# collpitss.net
KiCad netlist of a schematic drawn in EAGLE
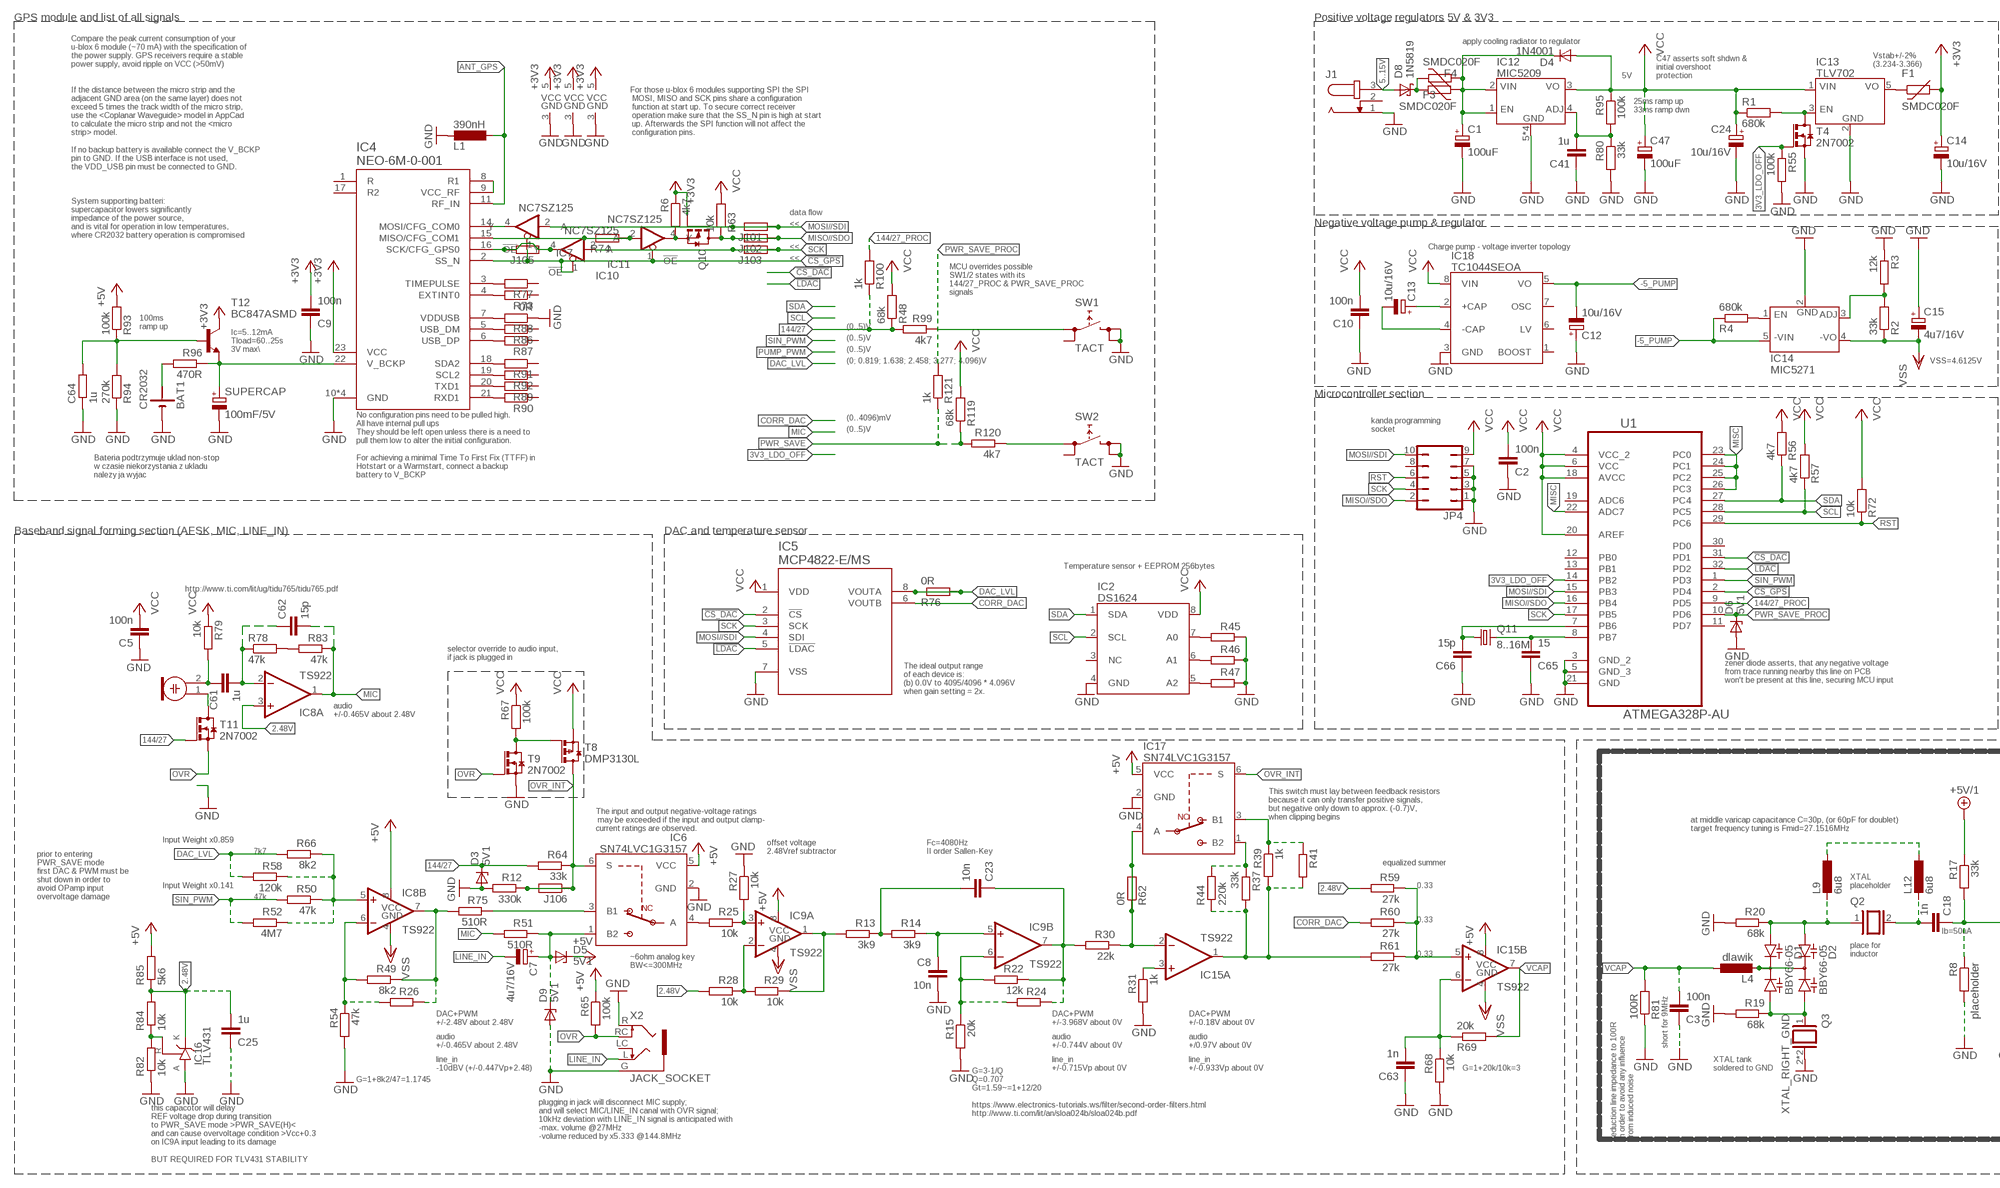
[diagram p0: schematic, sheet 1, part 1 of 2]
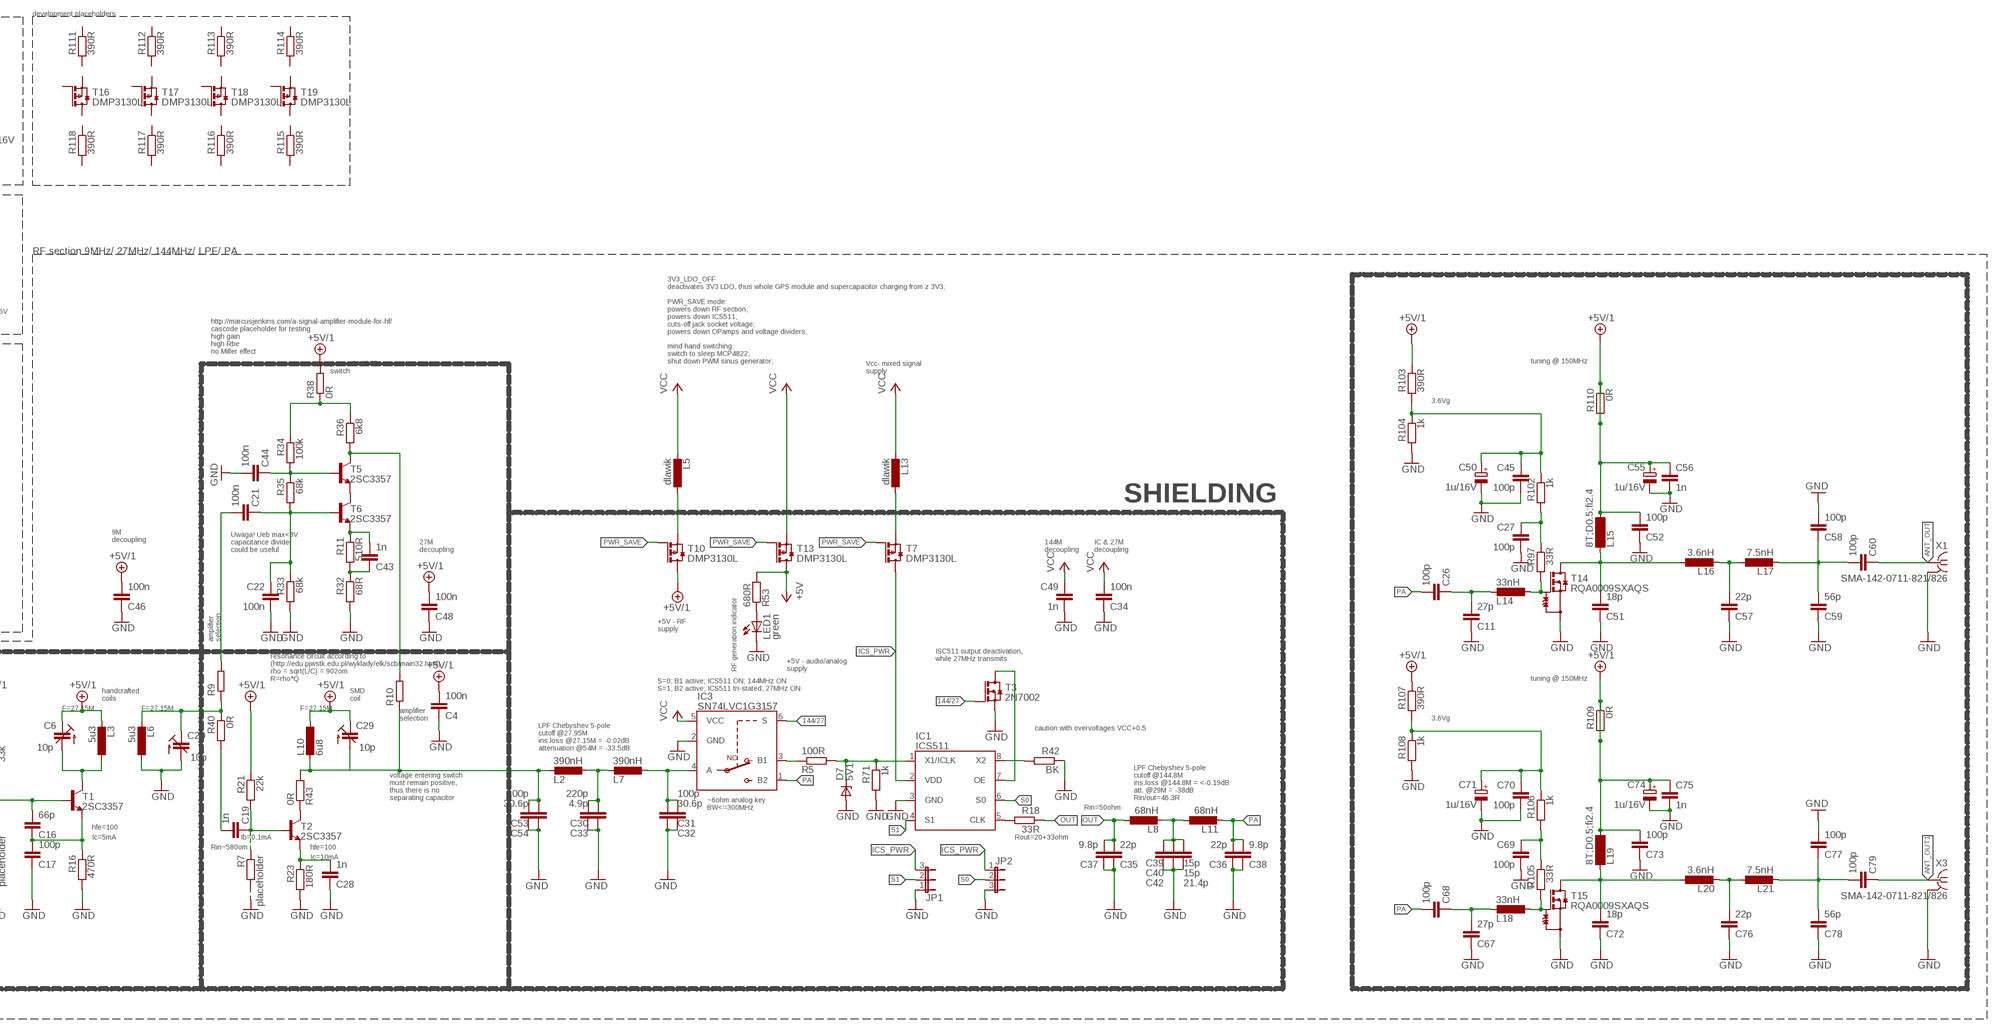
[diagram p1: schematic, sheet 1, part 2 of 2]

(export (version "E")
  (design (tool "Eeschema 10.0.6"))
  (components
    (comp (ref "BAT1")
      (value "CR2032")
      (footprint "eagle-import:CR2032_HOLDER")
      (libsource (lib "eagle-import") (part "CR2032"))
    )
    (comp (ref "C1")
      (value "100uF")
      (footprint "eagle-import:153CLV-0605")
      (libsource (lib "eagle-import") (part "CPOL-EU153CLV-0605"))
    )
    (comp (ref "C2")
      (value "100n")
      (footprint "eagle-import:C0805")
      (libsource (lib "eagle-import") (part "C-EUC0805"))
    )
    (comp (ref "C3")
      (value "100n")
      (footprint "eagle-import:C0805")
      (libsource (lib "eagle-import") (part "C-EUC0805"))
    )
    (comp (ref "C4")
      (value "100n")
      (footprint "eagle-import:C0805")
      (libsource (lib "eagle-import") (part "C-EUC0805"))
    )
    (comp (ref "C5")
      (value "100n")
      (footprint "eagle-import:C0805")
      (libsource (lib "eagle-import") (part "C-EUC0805"))
    )
    (comp (ref "C6")
      (value "10p")
      (footprint "eagle-import:TZC3_SERIES")
      (libsource (lib "eagle-import") (part "C_TRIMM"))
    )
    (comp (ref "C7")
      (value "4u7/16V")
      (footprint "eagle-import:TANTAL_3216_")
      (libsource (lib "eagle-import") (part "TANTAL_POLY{dblquote}3218{dblquote}"))
    )
    (comp (ref "C8")
      (value "10n")
      (footprint "eagle-import:C0805")
      (libsource (lib "eagle-import") (part "C-EUC0805"))
    )
    (comp (ref "C9")
      (value "100n")
      (footprint "eagle-import:C0805")
      (libsource (lib "eagle-import") (part "C-EUC0805"))
    )
    (comp (ref "C10")
      (value "100n")
      (footprint "eagle-import:C0805")
      (libsource (lib "eagle-import") (part "C-EUC0805"))
    )
    (comp (ref "C11")
      (value "27p")
      (footprint "eagle-import:C0805")
      (libsource (lib "eagle-import") (part "C-EUC0805"))
    )
    (comp (ref "C12")
      (value "10u/16V")
      (footprint "eagle-import:TANTAL_3216_")
      (libsource (lib "eagle-import") (part "TANTAL_POLY{dblquote}3218{dblquote}"))
    )
    (comp (ref "C13")
      (value "10u/16V")
      (footprint "eagle-import:TANTAL_3216_")
      (libsource (lib "eagle-import") (part "TANTAL_POLY{dblquote}3218{dblquote}"))
    )
    (comp (ref "C14")
      (value "10u/16V")
      (footprint "eagle-import:TANTAL_3216_")
      (libsource (lib "eagle-import") (part "TANTAL_POLY{dblquote}3218{dblquote}"))
    )
    (comp (ref "C15")
      (value "4u7/16V")
      (footprint "eagle-import:TANTAL_3216_")
      (libsource (lib "eagle-import") (part "TANTAL_POLY{dblquote}3218{dblquote}"))
    )
    (comp (ref "C16")
      (value "66p")
      (footprint "eagle-import:C0805")
      (libsource (lib "eagle-import") (part "C-EUC0805"))
    )
    (comp (ref "C17")
      (value "100p")
      (footprint "eagle-import:C0805")
      (libsource (lib "eagle-import") (part "C-EUC0805"))
    )
    (comp (ref "C18")
      (value "1n")
      (footprint "eagle-import:C0603K")
      (libsource (lib "eagle-import") (part "C-EUC0603K"))
    )
    (comp (ref "C19")
      (value "1n")
      (footprint "eagle-import:C0603K")
      (libsource (lib "eagle-import") (part "C-EUC0603K"))
    )
    (comp (ref "C20")
      (value "10p")
      (footprint "eagle-import:TZC3_SERIES")
      (libsource (lib "eagle-import") (part "C_TRIMM"))
    )
    (comp (ref "C21")
      (value "100n")
      (footprint "eagle-import:C0805")
      (libsource (lib "eagle-import") (part "C-EUC0805"))
    )
    (comp (ref "C22")
      (value "100n")
      (footprint "eagle-import:C0805")
      (libsource (lib "eagle-import") (part "C-EUC0805"))
    )
    (comp (ref "C23")
      (value "10n")
      (footprint "eagle-import:C0805")
      (libsource (lib "eagle-import") (part "C-EUC0805"))
    )
    (comp (ref "C24")
      (value "10u/16V")
      (footprint "eagle-import:TANTAL_3216_")
      (libsource (lib "eagle-import") (part "TANTAL_POLY{dblquote}3218{dblquote}"))
    )
    (comp (ref "C25")
      (value "1u")
      (footprint "eagle-import:C1206")
      (libsource (lib "eagle-import") (part "C-EUC1206"))
    )
    (comp (ref "C26")
      (value "100p")
      (footprint "eagle-import:C0805")
      (libsource (lib "eagle-import") (part "C-EUC0805"))
    )
    (comp (ref "C27")
      (value "100p")
      (footprint "eagle-import:C0805")
      (libsource (lib "eagle-import") (part "C-EUC0805"))
    )
    (comp (ref "C28")
      (value "1n")
      (footprint "eagle-import:C0603K")
      (libsource (lib "eagle-import") (part "C-EUC0603K"))
    )
    (comp (ref "C29")
      (value "10p")
      (footprint "eagle-import:TZC3_SERIES")
      (libsource (lib "eagle-import") (part "C_TRIMM"))
    )
    (comp (ref "C30")
      (value "220p")
      (footprint "eagle-import:C0805")
      (libsource (lib "eagle-import") (part "C-EUC0805"))
    )
    (comp (ref "C31")
      (value "100p")
      (footprint "eagle-import:C0805")
      (libsource (lib "eagle-import") (part "C-EUC0805"))
    )
    (comp (ref "C32")
      (value "30.6p")
      (footprint "eagle-import:C0805")
      (libsource (lib "eagle-import") (part "C-EUC0805"))
    )
    (comp (ref "C33")
      (value "4.9p")
      (footprint "eagle-import:C0805")
      (libsource (lib "eagle-import") (part "C-EUC0805"))
    )
    (comp (ref "C34")
      (value "100n")
      (footprint "eagle-import:C0805")
      (libsource (lib "eagle-import") (part "C-EUC0805"))
    )
    (comp (ref "C35")
      (value "22p")
      (footprint "eagle-import:C0805")
      (libsource (lib "eagle-import") (part "C-EUC0805"))
    )
    (comp (ref "C36")
      (value "22p")
      (footprint "eagle-import:C0805")
      (libsource (lib "eagle-import") (part "C-EUC0805"))
    )
    (comp (ref "C37")
      (value "9.8p")
      (footprint "eagle-import:C0805")
      (libsource (lib "eagle-import") (part "C-EUC0805"))
    )
    (comp (ref "C38")
      (value "9.8p")
      (footprint "eagle-import:C0805")
      (libsource (lib "eagle-import") (part "C-EUC0805"))
    )
    (comp (ref "C39")
      (value "15p")
      (footprint "eagle-import:C0805")
      (libsource (lib "eagle-import") (part "C-EUC0805"))
    )
    (comp (ref "C40")
      (value "21.4p")
      (footprint "eagle-import:C0805")
      (libsource (lib "eagle-import") (part "C-EUC0805"))
    )
    (comp (ref "C41")
      (value "1u")
      (footprint "eagle-import:C1206")
      (libsource (lib "eagle-import") (part "C-EUC1206"))
    )
    (comp (ref "C42")
      (value "15p")
      (footprint "eagle-import:C0805")
      (libsource (lib "eagle-import") (part "C-EUC0805"))
    )
    (comp (ref "C43")
      (value "1n")
      (footprint "eagle-import:C0603K")
      (libsource (lib "eagle-import") (part "C-EUC0603K"))
    )
    (comp (ref "C44")
      (value "100n")
      (footprint "eagle-import:C0805")
      (libsource (lib "eagle-import") (part "C-EUC0805"))
    )
    (comp (ref "C45")
      (value "100p")
      (footprint "eagle-import:C0805")
      (libsource (lib "eagle-import") (part "C-EUC0805"))
    )
    (comp (ref "C46")
      (value "100n")
      (footprint "eagle-import:C0805")
      (libsource (lib "eagle-import") (part "C-EUC0805"))
    )
    (comp (ref "C47")
      (value "100uF")
      (footprint "eagle-import:153CLV-0605")
      (libsource (lib "eagle-import") (part "CPOL-EU153CLV-0605"))
    )
    (comp (ref "C48")
      (value "100n")
      (footprint "eagle-import:C0805")
      (libsource (lib "eagle-import") (part "C-EUC0805"))
    )
    (comp (ref "C49")
      (value "1n")
      (footprint "eagle-import:C0603K")
      (libsource (lib "eagle-import") (part "C-EUC0603K"))
    )
    (comp (ref "C50")
      (value "1u/16V")
      (footprint "eagle-import:TANTAL_3216_")
      (libsource (lib "eagle-import") (part "TANTAL_POLY{dblquote}3218{dblquote}"))
    )
    (comp (ref "C51")
      (value "18p")
      (footprint "eagle-import:C0805")
      (libsource (lib "eagle-import") (part "C-EUC0805"))
    )
    (comp (ref "C52")
      (value "100p")
      (footprint "eagle-import:C0805")
      (libsource (lib "eagle-import") (part "C-EUC0805"))
    )
    (comp (ref "C53")
      (value "100p")
      (footprint "eagle-import:C0805")
      (libsource (lib "eagle-import") (part "C-EUC0805"))
    )
    (comp (ref "C54")
      (value "30.6p")
      (footprint "eagle-import:C0805")
      (libsource (lib "eagle-import") (part "C-EUC0805"))
    )
    (comp (ref "C55")
      (value "1u/16V")
      (footprint "eagle-import:TANTAL_3216_")
      (libsource (lib "eagle-import") (part "TANTAL_POLY{dblquote}3218{dblquote}"))
    )
    (comp (ref "C56")
      (value "1n")
      (footprint "eagle-import:C0603K")
      (libsource (lib "eagle-import") (part "C-EUC0603K"))
    )
    (comp (ref "C57")
      (value "22p")
      (footprint "eagle-import:C0805")
      (libsource (lib "eagle-import") (part "C-EUC0805"))
    )
    (comp (ref "C58")
      (value "100p")
      (footprint "eagle-import:C0805")
      (libsource (lib "eagle-import") (part "C-EUC0805"))
    )
    (comp (ref "C59")
      (value "56p")
      (footprint "eagle-import:C0805")
      (libsource (lib "eagle-import") (part "C-EUC0805"))
    )
    (comp (ref "C60")
      (value "100p")
      (footprint "eagle-import:C0805")
      (libsource (lib "eagle-import") (part "C-EUC0805"))
    )
    (comp (ref "C61")
      (value "1u")
      (footprint "eagle-import:ZWORA")
      (libsource (lib "eagle-import") (part "ZWORA_C"))
    )
    (comp (ref "C62")
      (value "15p")
      (footprint "eagle-import:C0805")
      (libsource (lib "eagle-import") (part "C-EUC0805"))
    )
    (comp (ref "C63")
      (value "1n")
      (footprint "eagle-import:C0603K")
      (libsource (lib "eagle-import") (part "C-EUC0603K"))
    )
    (comp (ref "C64")
      (value "1u")
      (footprint "eagle-import:ZWORA")
      (libsource (lib "eagle-import") (part "ZWORA"))
    )
    (comp (ref "C65")
      (value "15")
      (footprint "eagle-import:C0805")
      (libsource (lib "eagle-import") (part "C-EUC0805"))
    )
    (comp (ref "C66")
      (value "15p")
      (footprint "eagle-import:C0805")
      (libsource (lib "eagle-import") (part "C-EUC0805"))
    )
    (comp (ref "C67")
      (value "27p")
      (footprint "eagle-import:C0805")
      (libsource (lib "eagle-import") (part "C-EUC0805"))
    )
    (comp (ref "C68")
      (value "100p")
      (footprint "eagle-import:C0805")
      (libsource (lib "eagle-import") (part "C-EUC0805"))
    )
    (comp (ref "C69")
      (value "100p")
      (footprint "eagle-import:C0805")
      (libsource (lib "eagle-import") (part "C-EUC0805"))
    )
    (comp (ref "C70")
      (value "100p")
      (footprint "eagle-import:C0805")
      (libsource (lib "eagle-import") (part "C-EUC0805"))
    )
    (comp (ref "C71")
      (value "1u/16V")
      (footprint "eagle-import:TANTAL_3216_")
      (libsource (lib "eagle-import") (part "TANTAL_POLY{dblquote}3218{dblquote}"))
    )
    (comp (ref "C72")
      (value "18p")
      (footprint "eagle-import:C0805")
      (libsource (lib "eagle-import") (part "C-EUC0805"))
    )
    (comp (ref "C73")
      (value "100p")
      (footprint "eagle-import:C0805")
      (libsource (lib "eagle-import") (part "C-EUC0805"))
    )
    (comp (ref "C74")
      (value "1u/16V")
      (footprint "eagle-import:TANTAL_3216_")
      (libsource (lib "eagle-import") (part "TANTAL_POLY{dblquote}3218{dblquote}"))
    )
    (comp (ref "C75")
      (value "1n")
      (footprint "eagle-import:C0603K")
      (libsource (lib "eagle-import") (part "C-EUC0603K"))
    )
    (comp (ref "C76")
      (value "22p")
      (footprint "eagle-import:C0805")
      (libsource (lib "eagle-import") (part "C-EUC0805"))
    )
    (comp (ref "C77")
      (value "100p")
      (footprint "eagle-import:C0805")
      (libsource (lib "eagle-import") (part "C-EUC0805"))
    )
    (comp (ref "C78")
      (value "56p")
      (footprint "eagle-import:C0805")
      (libsource (lib "eagle-import") (part "C-EUC0805"))
    )
    (comp (ref "C79")
      (value "100p")
      (footprint "eagle-import:C0805")
      (libsource (lib "eagle-import") (part "C-EUC0805"))
    )
    (comp (ref "D1")
      (value "BBY66-05")
      (footprint "eagle-import:SOT23-3")
      (libsource (lib "eagle-import") (part "BBY66-05"))
    )
    (comp (ref "D2")
      (value "BBY66-05")
      (footprint "eagle-import:SOT23-3")
      (libsource (lib "eagle-import") (part "BBY66-05"))
    )
    (comp (ref "D3")
      (value "5V1")
      (footprint "eagle-import:SOD323")
      (libsource (lib "eagle-import") (part "1N4148"))
    )
    (comp (ref "D4")
      (value "1N4001")
      (footprint "eagle-import:DO-214AC")
      (libsource (lib "eagle-import") (part "1N4001"))
    )
    (comp (ref "D5")
      (value "5V1")
      (footprint "eagle-import:SOD323")
      (libsource (lib "eagle-import") (part "1N4148"))
    )
    (comp (ref "D6")
      (value "5V1")
      (footprint "eagle-import:SOD323")
      (libsource (lib "eagle-import") (part "1N4148"))
    )
    (comp (ref "D7")
      (value "5V1")
      (footprint "eagle-import:SOD323")
      (libsource (lib "eagle-import") (part "1N4148"))
    )
    (comp (ref "D8")
      (value "1N5819")
      (footprint "eagle-import:DO-214AC")
      (libsource (lib "eagle-import") (part "1N5819"))
    )
    (comp (ref "D9")
      (value "5V1")
      (footprint "eagle-import:SOD323")
      (libsource (lib "eagle-import") (part "1N4148"))
    )
    (comp (ref "F1")
      (value "SMDC020F")
      (footprint "eagle-import:1812")
      (libsource (lib "eagle-import") (part "SMDC020F"))
    )
    (comp (ref "F3")
      (value "SMDC020F")
      (footprint "eagle-import:1812")
      (libsource (lib "eagle-import") (part "SMDC020F"))
    )
    (comp (ref "F4")
      (value "SMDC020F")
      (footprint "eagle-import:1812")
      (libsource (lib "eagle-import") (part "SMDC020F"))
    )
    (comp (ref "IC1")
      (value "ICS511")
      (footprint "eagle-import:SOIC8")
      (libsource (lib "eagle-import") (part "ICS511"))
    )
    (comp (ref "IC2")
      (value "DS1624")
      (footprint "eagle-import:SOIC8")
      (libsource (lib "eagle-import") (part "DS1624"))
    )
    (comp (ref "IC3")
      (value "SN74LVC1G3157")
      (footprint "eagle-import:SC70-6")
      (libsource (lib "eagle-import") (part "SN74LVC1G3157"))
    )
    (comp (ref "IC4")
      (value "NEO-6M-0-001")
      (footprint "eagle-import:NEO-6M-0-001")
      (libsource (lib "eagle-import") (part "NEO-6M-0-001"))
    )
    (comp (ref "IC5")
      (value "MCP4822-E/MS")
      (footprint "eagle-import:SOP65P490X110-8N")
      (libsource (lib "eagle-import") (part "MCP4822-E/MS"))
    )
    (comp (ref "IC6")
      (value "SN74LVC1G3157")
      (footprint "eagle-import:SC70-6")
      (libsource (lib "eagle-import") (part "SN74LVC1G3157"))
    )
    (comp (ref "IC7")
      (value "NC7SZ125")
      (footprint "eagle-import:SC70-5")
      (libsource (lib "eagle-import") (part "NC7SZ125"))
    )
    (comp (ref "IC8")
      (value "TS922")
      (footprint "eagle-import:SO08")
      (libsource (lib "eagle-import") (part "TS922"))
    )
    (comp (ref "IC9")
      (value "TS922")
      (footprint "eagle-import:SO08")
      (libsource (lib "eagle-import") (part "TS922"))
    )
    (comp (ref "IC10")
      (value "NC7SZ125")
      (footprint "eagle-import:SC70-5")
      (libsource (lib "eagle-import") (part "NC7SZ125"))
    )
    (comp (ref "IC11")
      (value "NC7SZ125")
      (footprint "eagle-import:SC70-5")
      (libsource (lib "eagle-import") (part "NC7SZ125"))
    )
    (comp (ref "IC12")
      (value "MIC5209")
      (footprint "eagle-import:SOIC8")
      (libsource (lib "eagle-import") (part "MIC5209"))
    )
    (comp (ref "IC13")
      (value "TLV702")
      (footprint "eagle-import:SOT23-5")
      (libsource (lib "eagle-import") (part "TLV702"))
    )
    (comp (ref "IC14")
      (value "MIC5271")
      (footprint "eagle-import:SOT23-5")
      (libsource (lib "eagle-import") (part "MIC5271"))
    )
    (comp (ref "IC15")
      (value "TS922")
      (footprint "eagle-import:SO08")
      (libsource (lib "eagle-import") (part "TS922"))
    )
    (comp (ref "IC16")
      (value "TLV431")
      (footprint "eagle-import:SOT23-3")
      (libsource (lib "eagle-import") (part "TL431-ASA"))
    )
    (comp (ref "IC17")
      (value "SN74LVC1G3157")
      (footprint "eagle-import:SC70-6")
      (libsource (lib "eagle-import") (part "SN74LVC1G3157"))
    )
    (comp (ref "IC18")
      (value "TC1044SEOA")
      (footprint "eagle-import:SOIC8")
      (libsource (lib "eagle-import") (part "TC1044SEOA"))
    )
    (comp (ref "J1")
      (value "JACK-PLUG1")
      (footprint "eagle-import:SPC4078")
      (libsource (lib "eagle-import") (part "JACK-PLUG1"))
    )
    (comp (ref "J101")
      (value "ZWORA")
      (footprint "eagle-import:ZWORA")
      (libsource (lib "eagle-import") (part "ZWORA"))
    )
    (comp (ref "J102")
      (value "ZWORA")
      (footprint "eagle-import:ZWORA")
      (libsource (lib "eagle-import") (part "ZWORA"))
    )
    (comp (ref "J103")
      (value "ZWORA")
      (footprint "eagle-import:ZWORA")
      (libsource (lib "eagle-import") (part "ZWORA"))
    )
    (comp (ref "J105")
      (value "ZWORA")
      (footprint "eagle-import:ZWORA")
      (libsource (lib "eagle-import") (part "ZWORA"))
    )
    (comp (ref "J106")
      (value "ZWORA")
      (footprint "eagle-import:ZWORA")
      (libsource (lib "eagle-import") (part "ZWORA"))
    )
    (comp (ref "JP1")
      (value "JP2E")
      (footprint "eagle-import:JP2")
      (libsource (lib "eagle-import") (part "JP2E"))
    )
    (comp (ref "JP2")
      (value "JP2E")
      (footprint "eagle-import:JP2")
      (libsource (lib "eagle-import") (part "JP2E"))
    )
    (comp (ref "JP4")
      (value "JP5Q")
      (footprint "eagle-import:JP5Q")
      (libsource (lib "eagle-import") (part "JP5Q"))
    )
    (comp (ref "L1")
      (value "390nH")
      (footprint "eagle-import:0603K")
      (libsource (lib "eagle-import") (part "0603K_INDUCTOR"))
    )
    (comp (ref "L2")
      (value "390nH")
      (footprint "eagle-import:0603K")
      (libsource (lib "eagle-import") (part "0603K_INDUCTOR"))
    )
    (comp (ref "L3")
      (value "5u3")
      (footprint "eagle-import:L1812")
      (libsource (lib "eagle-import") (part "L-EUL1812"))
    )
    (comp (ref "L4")
      (value "dlawik")
      (footprint "eagle-import:0806")
      (libsource (lib "eagle-import") (part "0806_INDUCTOR"))
    )
    (comp (ref "L5")
      (value "dlawik")
      (footprint "eagle-import:0806")
      (libsource (lib "eagle-import") (part "0806_INDUCTOR"))
    )
    (comp (ref "L6")
      (value "5u3")
      (footprint "eagle-import:L1812")
      (libsource (lib "eagle-import") (part "L-EUL1812"))
    )
    (comp (ref "L7")
      (value "390nH")
      (footprint "eagle-import:0603K")
      (libsource (lib "eagle-import") (part "0603K_INDUCTOR"))
    )
    (comp (ref "L8")
      (value "68nH")
      (footprint "eagle-import:0805")
      (libsource (lib "eagle-import") (part "0805_INDUCTOR"))
    )
    (comp (ref "L9")
      (value "6u8")
      (footprint "eagle-import:1812")
      (libsource (lib "eagle-import") (part "1812_INDUCTOR"))
    )
    (comp (ref "L10")
      (value "6u8")
      (footprint "eagle-import:1812")
      (libsource (lib "eagle-import") (part "1812_INDUCTOR"))
    )
    (comp (ref "L11")
      (value "68nH")
      (footprint "eagle-import:0805")
      (libsource (lib "eagle-import") (part "0805_INDUCTOR"))
    )
    (comp (ref "L12")
      (value "6u8")
      (footprint "eagle-import:1812")
      (libsource (lib "eagle-import") (part "1812_INDUCTOR"))
    )
    (comp (ref "L13")
      (value "dlawik")
      (footprint "eagle-import:0806")
      (libsource (lib "eagle-import") (part "0806_INDUCTOR"))
    )
    (comp (ref "L14")
      (value "33nH")
      (footprint "eagle-import:0603K")
      (libsource (lib "eagle-import") (part "0603K_INDUCTOR"))
    )
    (comp (ref "L15")
      (value "8T;D0.5;fi2.4")
      (footprint "eagle-import:SM-Z15")
      (libsource (lib "eagle-import") (part "SM-Z15"))
    )
    (comp (ref "L16")
      (value "3.6nH")
      (footprint "eagle-import:0805")
      (libsource (lib "eagle-import") (part "0805_INDUCTOR"))
    )
    (comp (ref "L17")
      (value "7.5nH")
      (footprint "eagle-import:0805")
      (libsource (lib "eagle-import") (part "0805_INDUCTOR"))
    )
    (comp (ref "L18")
      (value "33nH")
      (footprint "eagle-import:0603K")
      (libsource (lib "eagle-import") (part "0603K_INDUCTOR"))
    )
    (comp (ref "L19")
      (value "8T;D0.5;fi2.4")
      (footprint "eagle-import:SM-Z15")
      (libsource (lib "eagle-import") (part "SM-Z15"))
    )
    (comp (ref "L20")
      (value "3.6nH")
      (footprint "eagle-import:0805")
      (libsource (lib "eagle-import") (part "0805_INDUCTOR"))
    )
    (comp (ref "L21")
      (value "7.5nH")
      (footprint "eagle-import:0805")
      (libsource (lib "eagle-import") (part "0805_INDUCTOR"))
    )
    (comp (ref "LED1")
      (value "green")
      (footprint "eagle-import:CHIP-LED0805")
      (libsource (lib "eagle-import") (part "LEDCHIP-LED0805"))
    )
    (comp (ref "M1")
      (value "ELECTRET_MICROPHON-WM-61A")
      (footprint "eagle-import:WM-61A")
      (libsource (lib "eagle-import") (part "ELECTRET_MICROPHON-WM-61A"))
    )
    (comp (ref "Q2")
      (value "XTAL\"")
      (footprint "eagle-import:Q_")
      (libsource (lib "eagle-import") (part "XTAL{dblquote}"))
    )
    (comp (ref "Q3")
      (value "XTAL_RIGHT_GND")
      (footprint "eagle-import:Q")
      (libsource (lib "eagle-import") (part "XTAL_RIGHT_GND"))
    )
    (comp (ref "Q10")
      (value "AO3402")
      (footprint "eagle-import:SOT23-3")
      (libsource (lib "eagle-import") (part "AO3402"))
    )
    (comp (ref "Q11")
      (value "8..16M")
      (footprint "eagle-import:SM49")
      (libsource (lib "eagle-import") (part "CRYSTALSM49"))
    )
    (comp (ref "R1")
      (value "680k")
      (footprint "eagle-import:ZWORA")
      (libsource (lib "eagle-import") (part "ZWORA"))
    )
    (comp (ref "R2")
      (value "33k")
      (footprint "eagle-import:R0805")
      (libsource (lib "eagle-import") (part "resistor_R-EU_R0805"))
    )
    (comp (ref "R3")
      (value "12k")
      (footprint "eagle-import:R0805")
      (libsource (lib "eagle-import") (part "resistor_R-EU_R0805"))
    )
    (comp (ref "R4")
      (value "680k")
      (footprint "eagle-import:R0805")
      (libsource (lib "eagle-import") (part "resistor_R-EU_R0805"))
    )
    (comp (ref "R5")
      (value "100R")
      (footprint "eagle-import:R0805")
      (libsource (lib "eagle-import") (part "R-EU_R0805"))
    )
    (comp (ref "R6")
      (value "4k7")
      (footprint "eagle-import:R0805")
      (libsource (lib "eagle-import") (part "resistor_R-EU_R0805"))
    )
    (comp (ref "R7")
      (value "placeholder")
      (footprint "eagle-import:R0805")
      (libsource (lib "eagle-import") (part "resistor_R-EU_R0805"))
    )
    (comp (ref "R8")
      (value "placeholder")
      (footprint "eagle-import:R0805")
      (libsource (lib "eagle-import") (part "resistor_R-EU_R0805"))
    )
    (comp (ref "R9")
      (value "ZWORA")
      (footprint "eagle-import:ZWORA")
      (libsource (lib "eagle-import") (part "ZWORA"))
    )
    (comp (ref "R10")
      (value "ZWORA")
      (footprint "eagle-import:ZWORA")
      (libsource (lib "eagle-import") (part "ZWORA"))
    )
    (comp (ref "R11")
      (value "510R")
      (footprint "eagle-import:R0805")
      (libsource (lib "eagle-import") (part "resistor_R-EU_R0805"))
    )
    (comp (ref "R12")
      (value "330k")
      (footprint "eagle-import:R0805")
      (libsource (lib "eagle-import") (part "resistor_R-EU_R0805"))
    )
    (comp (ref "R13")
      (value "3k9")
      (footprint "eagle-import:R0805")
      (libsource (lib "eagle-import") (part "resistor_R-EU_R0805"))
    )
    (comp (ref "R14")
      (value "3k9")
      (footprint "eagle-import:R0805")
      (libsource (lib "eagle-import") (part "resistor_R-EU_R0805"))
    )
    (comp (ref "R15")
      (value "20k")
      (footprint "eagle-import:R0805")
      (libsource (lib "eagle-import") (part "resistor_R-EU_R0805"))
    )
    (comp (ref "R16")
      (value "470R")
      (footprint "eagle-import:R0805")
      (libsource (lib "eagle-import") (part "resistor_R-EU_R0805"))
    )
    (comp (ref "R17")
      (value "33k")
      (footprint "eagle-import:R0805")
      (libsource (lib "eagle-import") (part "resistor_R-EU_R0805"))
    )
    (comp (ref "R18")
      (value "33R")
      (footprint "eagle-import:R0805")
      (libsource (lib "eagle-import") (part "R-EU_R0805"))
    )
    (comp (ref "R19")
      (value "68k")
      (footprint "eagle-import:R0805")
      (libsource (lib "eagle-import") (part "resistor_R-EU_R0805"))
    )
    (comp (ref "R20")
      (value "68k")
      (footprint "eagle-import:R0805")
      (libsource (lib "eagle-import") (part "resistor_R-EU_R0805"))
    )
    (comp (ref "R21")
      (value "22k")
      (footprint "eagle-import:R0805")
      (libsource (lib "eagle-import") (part "resistor_R-EU_R0805"))
    )
    (comp (ref "R22")
      (value "12k")
      (footprint "eagle-import:R0805")
      (libsource (lib "eagle-import") (part "resistor_R-EU_R0805"))
    )
    (comp (ref "R23")
      (value "180R")
      (footprint "eagle-import:R0805")
      (libsource (lib "eagle-import") (part "resistor_R-EU_R0805"))
    )
    (comp (ref "R24")
      (value "R-EU_R0805")
      (footprint "eagle-import:R0805")
      (libsource (lib "eagle-import") (part "resistor_R-EU_R0805"))
    )
    (comp (ref "R25")
      (value "10k")
      (footprint "eagle-import:R0805")
      (libsource (lib "eagle-import") (part "resistor_R-EU_R0805"))
    )
    (comp (ref "R26")
      (value "R-EU_R0805")
      (footprint "eagle-import:R0805")
      (libsource (lib "eagle-import") (part "resistor_R-EU_R0805"))
    )
    (comp (ref "R27")
      (value "10k")
      (footprint "eagle-import:R0805")
      (libsource (lib "eagle-import") (part "resistor_R-EU_R0805"))
    )
    (comp (ref "R28")
      (value "10k")
      (footprint "eagle-import:R0805")
      (libsource (lib "eagle-import") (part "resistor_R-EU_R0805"))
    )
    (comp (ref "R29")
      (value "10k")
      (footprint "eagle-import:R0805")
      (libsource (lib "eagle-import") (part "resistor_R-EU_R0805"))
    )
    (comp (ref "R30")
      (value "22k")
      (footprint "eagle-import:R0805")
      (libsource (lib "eagle-import") (part "resistor_R-EU_R0805"))
    )
    (comp (ref "R31")
      (value "1k")
      (footprint "eagle-import:R0805")
      (libsource (lib "eagle-import") (part "resistor_R-EU_R0805"))
    )
    (comp (ref "R32")
      (value "68R")
      (footprint "eagle-import:ZWORA")
      (libsource (lib "eagle-import") (part "ZWORA"))
    )
    (comp (ref "R33")
      (value "68k")
      (footprint "eagle-import:R0805")
      (libsource (lib "eagle-import") (part "resistor_R-EU_R0805"))
    )
    (comp (ref "R34")
      (value "100k")
      (footprint "eagle-import:R0805")
      (libsource (lib "eagle-import") (part "resistor_R-EU_R0805"))
    )
    (comp (ref "R35")
      (value "68k")
      (footprint "eagle-import:R0805")
      (libsource (lib "eagle-import") (part "resistor_R-EU_R0805"))
    )
    (comp (ref "R36")
      (value "6k8")
      (footprint "eagle-import:R0805")
      (libsource (lib "eagle-import") (part "resistor_R-EU_R0805"))
    )
    (comp (ref "R37")
      (value "33k")
      (footprint "eagle-import:R0805")
      (libsource (lib "eagle-import") (part "resistor_R-EU_R0805"))
    )
    (comp (ref "R38")
      (value "0R")
      (footprint "eagle-import:R1206")
      (libsource (lib "eagle-import") (part "resistor_R-EU_R1206"))
    )
    (comp (ref "R39")
      (value "1k")
      (footprint "eagle-import:R0805")
      (libsource (lib "eagle-import") (part "resistor_R-EU_R0805"))
    )
    (comp (ref "R40")
      (value "0R")
      (footprint "eagle-import:R1206")
      (libsource (lib "eagle-import") (part "resistor_R-EU_R1206"))
    )
    (comp (ref "R41")
      (value "R-EU_R0805")
      (footprint "eagle-import:R0805")
      (libsource (lib "eagle-import") (part "resistor_R-EU_R0805"))
    )
    (comp (ref "R42")
      (value "BK")
      (footprint "eagle-import:R0805")
      (libsource (lib "eagle-import") (part "R-EU_R0805"))
    )
    (comp (ref "R43")
      (value "0R")
      (footprint "eagle-import:R1206")
      (libsource (lib "eagle-import") (part "resistor_R-EU_R1206"))
    )
    (comp (ref "R44")
      (value "220k")
      (footprint "eagle-import:R0805")
      (libsource (lib "eagle-import") (part "resistor_R-EU_R0805"))
    )
    (comp (ref "R45")
      (value "R-EU_R0805")
      (footprint "eagle-import:R0805")
      (libsource (lib "eagle-import") (part "resistor_R-EU_R0805"))
    )
    (comp (ref "R46")
      (value "R-EU_R0805")
      (footprint "eagle-import:R0805")
      (libsource (lib "eagle-import") (part "resistor_R-EU_R0805"))
    )
    (comp (ref "R47")
      (value "R-EU_R0805")
      (footprint "eagle-import:R0805")
      (libsource (lib "eagle-import") (part "resistor_R-EU_R0805"))
    )
    (comp (ref "R48")
      (value "68k")
      (footprint "eagle-import:R0805")
      (libsource (lib "eagle-import") (part "resistor_R-EU_R0805"))
    )
    (comp (ref "R49")
      (value "8k2")
      (footprint "eagle-import:R0805")
      (libsource (lib "eagle-import") (part "resistor_R-EU_R0805"))
    )
    (comp (ref "R50")
      (value "47k")
      (footprint "eagle-import:R0805")
      (libsource (lib "eagle-import") (part "resistor_R-EU_R0805"))
    )
    (comp (ref "R51")
      (value "510R")
      (footprint "eagle-import:R0805")
      (libsource (lib "eagle-import") (part "resistor_R-EU_R0805"))
    )
    (comp (ref "R52")
      (value "4M7")
      (footprint "eagle-import:R0805")
      (libsource (lib "eagle-import") (part "resistor_R-EU_R0805"))
    )
    (comp (ref "R53")
      (value "680R")
      (footprint "eagle-import:ZWORA")
      (libsource (lib "eagle-import") (part "ZWORA"))
    )
    (comp (ref "R54")
      (value "47k")
      (footprint "eagle-import:R0805")
      (libsource (lib "eagle-import") (part "resistor_R-EU_R0805"))
    )
    (comp (ref "R55")
      (value "100k")
      (footprint "eagle-import:R0805")
      (libsource (lib "eagle-import") (part "resistor_R-EU_R0805"))
    )
    (comp (ref "R56")
      (value "4k7")
      (footprint "eagle-import:R0805")
      (libsource (lib "eagle-import") (part "resistor_R-EU_R0805"))
    )
    (comp (ref "R57")
      (value "4k7")
      (footprint "eagle-import:ZWORA")
      (libsource (lib "eagle-import") (part "ZWORA"))
    )
    (comp (ref "R58")
      (value "120k")
      (footprint "eagle-import:R0805")
      (libsource (lib "eagle-import") (part "resistor_R-EU_R0805"))
    )
    (comp (ref "R59")
      (value "27k")
      (footprint "eagle-import:R0805")
      (libsource (lib "eagle-import") (part "resistor_R-EU_R0805"))
    )
    (comp (ref "R60")
      (value "27k")
      (footprint "eagle-import:R0805")
      (libsource (lib "eagle-import") (part "resistor_R-EU_R0805"))
    )
    (comp (ref "R61")
      (value "27k")
      (footprint "eagle-import:R0805")
      (libsource (lib "eagle-import") (part "resistor_R-EU_R0805"))
    )
    (comp (ref "R62")
      (value "0R")
      (footprint "eagle-import:ZWORA")
      (libsource (lib "eagle-import") (part "ZWORA"))
    )
    (comp (ref "R63")
      (value "10k")
      (footprint "eagle-import:R0805")
      (libsource (lib "eagle-import") (part "resistor_R-EU_R0805"))
    )
    (comp (ref "R64")
      (value "33k")
      (footprint "eagle-import:R0805")
      (libsource (lib "eagle-import") (part "resistor_R-EU_R0805"))
    )
    (comp (ref "R65")
      (value "100k")
      (footprint "eagle-import:ZWORA")
      (libsource (lib "eagle-import") (part "ZWORA"))
    )
    (comp (ref "R66")
      (value "8k2")
      (footprint "eagle-import:R0805")
      (libsource (lib "eagle-import") (part "resistor_R-EU_R0805"))
    )
    (comp (ref "R67")
      (value "100k")
      (footprint "eagle-import:R0805")
      (libsource (lib "eagle-import") (part "resistor_R-EU_R0805"))
    )
    (comp (ref "R68")
      (value "10k")
      (footprint "eagle-import:R0805")
      (libsource (lib "eagle-import") (part "resistor_R-EU_R0805"))
    )
    (comp (ref "R69")
      (value "20k")
      (footprint "eagle-import:R0805")
      (libsource (lib "eagle-import") (part "resistor_R-EU_R0805"))
    )
    (comp (ref "R71")
      (value "1k")
      (footprint "eagle-import:R0805")
      (libsource (lib "eagle-import") (part "R-EU_R0805"))
    )
    (comp (ref "R72")
      (value "10k")
      (footprint "eagle-import:R0805")
      (libsource (lib "eagle-import") (part "resistor_R-EU_R0805"))
    )
    (comp (ref "R73")
      (value "R-EU_R0805")
      (footprint "eagle-import:R0805")
      (libsource (lib "eagle-import") (part "resistor_R-EU_R0805"))
    )
    (comp (ref "R74")
      (value "ZWORA")
      (footprint "eagle-import:ZWORA")
      (libsource (lib "eagle-import") (part "ZWORA"))
    )
    (comp (ref "R75")
      (value "510R")
      (footprint "eagle-import:R0805")
      (libsource (lib "eagle-import") (part "resistor_R-EU_R0805"))
    )
    (comp (ref "R76")
      (value "0R")
      (footprint "eagle-import:ZWORA")
      (libsource (lib "eagle-import") (part "ZWORA"))
    )
    (comp (ref "R77")
      (value "R-EU_R0805")
      (footprint "eagle-import:R0805")
      (libsource (lib "eagle-import") (part "resistor_R-EU_R0805"))
    )
    (comp (ref "R78")
      (value "47k")
      (footprint "eagle-import:R0805")
      (libsource (lib "eagle-import") (part "resistor_R-EU_R0805"))
    )
    (comp (ref "R79")
      (value "10k")
      (footprint "eagle-import:R0805")
      (libsource (lib "eagle-import") (part "resistor_R-EU_R0805"))
    )
    (comp (ref "R80")
      (value "33k")
      (footprint "eagle-import:R0805")
      (libsource (lib "eagle-import") (part "resistor_R-EU_R0805"))
    )
    (comp (ref "R81")
      (value "100R")
      (footprint "eagle-import:R0805")
      (libsource (lib "eagle-import") (part "resistor_R-EU_R0805"))
    )
    (comp (ref "R82")
      (value "10k")
      (footprint "eagle-import:R0805")
      (libsource (lib "eagle-import") (part "resistor_R-EU_R0805"))
    )
    (comp (ref "R83")
      (value "47k")
      (footprint "eagle-import:R0805")
      (libsource (lib "eagle-import") (part "resistor_R-EU_R0805"))
    )
    (comp (ref "R84")
      (value "10k")
      (footprint "eagle-import:R0805")
      (libsource (lib "eagle-import") (part "resistor_R-EU_R0805"))
    )
    (comp (ref "R85")
      (value "5k6")
      (footprint "eagle-import:R0805")
      (libsource (lib "eagle-import") (part "resistor_R-EU_R0805"))
    )
    (comp (ref "R86")
      (value "R-EU_R0805")
      (footprint "eagle-import:R0805")
      (libsource (lib "eagle-import") (part "resistor_R-EU_R0805"))
    )
    (comp (ref "R87")
      (value "R-EU_R0805")
      (footprint "eagle-import:R0805")
      (libsource (lib "eagle-import") (part "resistor_R-EU_R0805"))
    )
    (comp (ref "R88")
      (value "0R")
      (footprint "eagle-import:R0805")
      (libsource (lib "eagle-import") (part "resistor_R-EU_R0805"))
    )
    (comp (ref "R89")
      (value "R-EU_R0805")
      (footprint "eagle-import:R0805")
      (libsource (lib "eagle-import") (part "resistor_R-EU_R0805"))
    )
    (comp (ref "R90")
      (value "R-EU_R0805")
      (footprint "eagle-import:R0805")
      (libsource (lib "eagle-import") (part "resistor_R-EU_R0805"))
    )
    (comp (ref "R91")
      (value "R-EU_R0805")
      (footprint "eagle-import:R0805")
      (libsource (lib "eagle-import") (part "resistor_R-EU_R0805"))
    )
    (comp (ref "R92")
      (value "R-EU_R0805")
      (footprint "eagle-import:R0805")
      (libsource (lib "eagle-import") (part "resistor_R-EU_R0805"))
    )
    (comp (ref "R93")
      (value "100k")
      (footprint "eagle-import:R0805")
      (libsource (lib "eagle-import") (part "resistor_R-EU_R0805"))
    )
    (comp (ref "R94")
      (value "270k")
      (footprint "eagle-import:ZWORA")
      (libsource (lib "eagle-import") (part "ZWORA"))
    )
    (comp (ref "R95")
      (value "100k")
      (footprint "eagle-import:R0805")
      (libsource (lib "eagle-import") (part "resistor_R-EU_R0805"))
    )
    (comp (ref "R96")
      (value "470R")
      (footprint "eagle-import:ZWORA")
      (libsource (lib "eagle-import") (part "ZWORA"))
    )
    (comp (ref "R97")
      (value "33R")
      (footprint "eagle-import:R0805")
      (libsource (lib "eagle-import") (part "R-EU_R0805"))
    )
    (comp (ref "R99")
      (value "4k7")
      (footprint "eagle-import:R0805")
      (libsource (lib "eagle-import") (part "resistor_R-EU_R0805"))
    )
    (comp (ref "R100")
      (value "1k")
      (footprint "eagle-import:R0805")
      (libsource (lib "eagle-import") (part "resistor_R-EU_R0805"))
    )
    (comp (ref "R102")
      (value "1k")
      (footprint "eagle-import:R0805")
      (libsource (lib "eagle-import") (part "R-EU_R0805"))
    )
    (comp (ref "R103")
      (value "390R")
      (footprint "eagle-import:R0805")
      (libsource (lib "eagle-import") (part "R-EU_R0805"))
    )
    (comp (ref "R104")
      (value "1k")
      (footprint "eagle-import:R0805")
      (libsource (lib "eagle-import") (part "R-EU_R0805"))
    )
    (comp (ref "R105")
      (value "33R")
      (footprint "eagle-import:R0805")
      (libsource (lib "eagle-import") (part "R-EU_R0805"))
    )
    (comp (ref "R106")
      (value "1k")
      (footprint "eagle-import:R0805")
      (libsource (lib "eagle-import") (part "R-EU_R0805"))
    )
    (comp (ref "R107")
      (value "390R")
      (footprint "eagle-import:R0805")
      (libsource (lib "eagle-import") (part "R-EU_R0805"))
    )
    (comp (ref "R108")
      (value "1k")
      (footprint "eagle-import:R0805")
      (libsource (lib "eagle-import") (part "R-EU_R0805"))
    )
    (comp (ref "R109")
      (value "0R")
      (footprint "eagle-import:ZWORA")
      (libsource (lib "eagle-import") (part "ZWORA"))
    )
    (comp (ref "R110")
      (value "0R")
      (footprint "eagle-import:ZWORA")
      (libsource (lib "eagle-import") (part "ZWORA"))
    )
    (comp (ref "R111")
      (value "390R")
      (footprint "eagle-import:R0805")
      (libsource (lib "eagle-import") (part "R-EU_R0805"))
    )
    (comp (ref "R112")
      (value "390R")
      (footprint "eagle-import:R0805")
      (libsource (lib "eagle-import") (part "R-EU_R0805"))
    )
    (comp (ref "R113")
      (value "390R")
      (footprint "eagle-import:R0805")
      (libsource (lib "eagle-import") (part "R-EU_R0805"))
    )
    (comp (ref "R114")
      (value "390R")
      (footprint "eagle-import:R0805")
      (libsource (lib "eagle-import") (part "R-EU_R0805"))
    )
    (comp (ref "R115")
      (value "390R")
      (footprint "eagle-import:R0805")
      (libsource (lib "eagle-import") (part "R-EU_R0805"))
    )
    (comp (ref "R116")
      (value "390R")
      (footprint "eagle-import:R0805")
      (libsource (lib "eagle-import") (part "R-EU_R0805"))
    )
    (comp (ref "R117")
      (value "390R")
      (footprint "eagle-import:R0805")
      (libsource (lib "eagle-import") (part "R-EU_R0805"))
    )
    (comp (ref "R118")
      (value "390R")
      (footprint "eagle-import:R0805")
      (libsource (lib "eagle-import") (part "R-EU_R0805"))
    )
    (comp (ref "R119")
      (value "68k")
      (footprint "eagle-import:R0805")
      (libsource (lib "eagle-import") (part "resistor_R-EU_R0805"))
    )
    (comp (ref "R120")
      (value "4k7")
      (footprint "eagle-import:R0805")
      (libsource (lib "eagle-import") (part "resistor_R-EU_R0805"))
    )
    (comp (ref "R121")
      (value "1k")
      (footprint "eagle-import:ZWORA")
      (libsource (lib "eagle-import") (part "ZWORA"))
    )
    (comp (ref "SUPERCAP")
      (value "100mF/5V")
      (footprint "eagle-import:UD-10X10_NICHICON")
      (libsource (lib "eagle-import") (part "CPOL-EUUD-10X10"))
    )
    (comp (ref "SW1")
      (value "TACT")
      (footprint "eagle-import:TACT")
      (libsource (lib "eagle-import") (part "TACT"))
    )
    (comp (ref "SW2")
      (value "TACT")
      (footprint "eagle-import:TACT")
      (libsource (lib "eagle-import") (part "TACT"))
    )
    (comp (ref "T1")
      (value "2SC3357")
      (footprint "eagle-import:SOT-89-BCE")
      (libsource (lib "eagle-import") (part "2SC3357"))
    )
    (comp (ref "T2")
      (value "2SC3357")
      (footprint "eagle-import:SOT-89-BCE")
      (libsource (lib "eagle-import") (part "2SC3357"))
    )
    (comp (ref "T3")
      (value "2N7002")
      (footprint "eagle-import:SOT23-3W")
      (libsource (lib "eagle-import") (part "2N7002"))
    )
    (comp (ref "T4")
      (value "2N7002")
      (footprint "eagle-import:SOT23-3W")
      (libsource (lib "eagle-import") (part "2N7002"))
    )
    (comp (ref "T5")
      (value "2SC3357")
      (footprint "eagle-import:SOT-89-BCE")
      (libsource (lib "eagle-import") (part "2SC3357"))
    )
    (comp (ref "T6")
      (value "2SC3357")
      (footprint "eagle-import:SOT-89-BCE")
      (libsource (lib "eagle-import") (part "2SC3357"))
    )
    (comp (ref "T7")
      (value "DMP3130L")
      (footprint "eagle-import:SOT23-3")
      (libsource (lib "eagle-import") (part "DMP3130L"))
    )
    (comp (ref "T8")
      (value "DMP3130L")
      (footprint "eagle-import:SOT23-3")
      (libsource (lib "eagle-import") (part "DMP3130L"))
    )
    (comp (ref "T9")
      (value "2N7002")
      (footprint "eagle-import:SOT23-3W")
      (libsource (lib "eagle-import") (part "2N7002"))
    )
    (comp (ref "T10")
      (value "DMP3130L")
      (footprint "eagle-import:SOT23-3")
      (libsource (lib "eagle-import") (part "DMP3130L"))
    )
    (comp (ref "T11")
      (value "2N7002")
      (footprint "eagle-import:SOT23-3W")
      (libsource (lib "eagle-import") (part "2N7002"))
    )
    (comp (ref "T12")
      (value "BC847ASMD")
      (footprint "eagle-import:SOT23")
      (libsource (lib "eagle-import") (part "BC847SMDA"))
    )
    (comp (ref "T13")
      (value "DMP3130L")
      (footprint "eagle-import:SOT23-3")
      (libsource (lib "eagle-import") (part "DMP3130L"))
    )
    (comp (ref "T14")
      (value "RQA0009SXAQS")
      (footprint "eagle-import:SOT-89-GSD")
      (libsource (lib "eagle-import") (part "RQA0009SXAQS"))
    )
    (comp (ref "T15")
      (value "RQA0009SXAQS")
      (footprint "eagle-import:SOT-89-GSD")
      (libsource (lib "eagle-import") (part "RQA0009SXAQS"))
    )
    (comp (ref "T16")
      (value "DMP3130L")
      (footprint "eagle-import:SOT23-3")
      (libsource (lib "eagle-import") (part "DMP3130L"))
    )
    (comp (ref "T17")
      (value "DMP3130L")
      (footprint "eagle-import:SOT23-3")
      (libsource (lib "eagle-import") (part "DMP3130L"))
    )
    (comp (ref "T18")
      (value "DMP3130L")
      (footprint "eagle-import:SOT23-3")
      (libsource (lib "eagle-import") (part "DMP3130L"))
    )
    (comp (ref "T19")
      (value "DMP3130L")
      (footprint "eagle-import:SOT23-3")
      (libsource (lib "eagle-import") (part "DMP3130L"))
    )
    (comp (ref "U1")
      (value "ATMEGA328P-AU")
      (footprint "eagle-import:QFP80P900X900X120-32N")
      (libsource (lib "eagle-import") (part "ATMEGA328P-AU"))
    )
    (comp (ref "X1")
      (value "SMA-142-0711-821/826")
      (footprint "eagle-import:J502-ND-142-0711-821_826")
      (fields (field (name "MF") "JOHNSON COMPONENTS") (field (name "MPN") "142-0711-821"))
      (libsource (lib "eagle-import") (part "SMA-142-0711-821/826"))
    )
    (comp (ref "X2")
      (value "JACK_SOCKET")
      (footprint "eagle-import:JACK_SOCKET")
      (libsource (lib "eagle-import") (part "JACK_SOCKET"))
    )
    (comp (ref "X3")
      (value "SMA-142-0711-821/826")
      (footprint "eagle-import:J502-ND-142-0711-821_826")
      (fields (field (name "MF") "JOHNSON COMPONENTS") (field (name "MPN") "142-0711-821"))
      (libsource (lib "eagle-import") (part "SMA-142-0711-821/826"))
    )
  )
  (nets
    (net (code "1") (name "+3V3") (class "Default")
      (node (ref "C14") (pin "+") (pinfunction "+_+") (pintype "passive"))
      (node (ref "C9") (pin "2") (pinfunction "2_2") (pintype "passive"))
      (node (ref "F1") (pin "P$2") (pinfunction "2_P$2") (pintype "passive"))
      (node (ref "IC10") (pin "5") (pinfunction "VCC_5") (pintype "power_in"))
      (node (ref "IC11") (pin "5") (pinfunction "VCC_5") (pintype "power_in"))
      (node (ref "IC4") (pin "23") (pinfunction "VCC_23") (pintype "power_in"))
      (node (ref "IC7") (pin "5") (pinfunction "VCC_5") (pintype "power_in"))
      (node (ref "Q10") (pin "1") (pinfunction "G_1") (pintype "passive"))
      (node (ref "R6") (pin "1") (pinfunction "1_1") (pintype "passive"))
      (node (ref "T12") (pin "3") (pinfunction "C_3") (pintype "passive"))
    )
    (net (code "2") (name "+5V") (class "Default")
      (node (ref "D5") (pin "C") (pinfunction "K_C") (pintype "passive"))
      (node (ref "IC15") (pin "8") (pinfunction "VCC_8") (pintype "power_in"))
      (node (ref "IC17") (pin "5") (pinfunction "VCC_5") (pintype "input"))
      (node (ref "IC6") (pin "5") (pinfunction "VCC_5") (pintype "input"))
      (node (ref "IC8") (pin "8") (pinfunction "VCC_8") (pintype "power_in"))
      (node (ref "IC9") (pin "8") (pinfunction "VCC_8") (pintype "power_in"))
      (node (ref "R53") (pin "2") (pinfunction "2_2") (pintype "passive"))
      (node (ref "R65") (pin "1") (pinfunction "1_1") (pintype "passive"))
      (node (ref "R85") (pin "2") (pinfunction "2_2") (pintype "passive"))
      (node (ref "R93") (pin "2") (pinfunction "2_2") (pintype "passive"))
      (node (ref "T13") (pin "3") (pinfunction "D_3") (pintype "passive"))
    )
    (net (code "3") (name "+5V{slash}1") (class "Default")
      (node (ref "C29") (pin "2") (pinfunction "E_2") (pintype "passive"))
      (node (ref "C4") (pin "2") (pinfunction "2_2") (pintype "passive"))
      (node (ref "C46") (pin "2") (pinfunction "2_2") (pintype "passive"))
      (node (ref "C48") (pin "2") (pinfunction "2_2") (pintype "passive"))
      (node (ref "C52") (pin "2") (pinfunction "2_2") (pintype "passive"))
      (node (ref "C55") (pin "+") (pinfunction "+_+") (pintype "passive"))
      (node (ref "C56") (pin "1") (pinfunction "1_1") (pintype "passive"))
      (node (ref "C6") (pin "2") (pinfunction "E_2") (pintype "passive"))
      (node (ref "C73") (pin "2") (pinfunction "2_2") (pintype "passive"))
      (node (ref "C74") (pin "+") (pinfunction "+_+") (pintype "passive"))
      (node (ref "C75") (pin "1") (pinfunction "1_1") (pintype "passive"))
      (node (ref "L10") (pin "1") (pinfunction "1_1") (pintype "passive"))
      (node (ref "L15") (pin "2") (pinfunction "2_2") (pintype "passive"))
      (node (ref "L19") (pin "2") (pinfunction "2_2") (pintype "passive"))
      (node (ref "L3") (pin "2") (pinfunction "2_2") (pintype "passive"))
      (node (ref "R103") (pin "1") (pinfunction "1_1") (pintype "passive"))
      (node (ref "R107") (pin "1") (pinfunction "1_1") (pintype "passive"))
      (node (ref "R109") (pin "1") (pinfunction "1_1") (pintype "passive"))
      (node (ref "R109") (pin "2") (pinfunction "2_2") (pintype "passive"))
      (node (ref "R110") (pin "1") (pinfunction "1_1") (pintype "passive"))
      (node (ref "R110") (pin "2") (pinfunction "2_2") (pintype "passive"))
      (node (ref "R17") (pin "1") (pinfunction "1_1") (pintype "passive"))
      (node (ref "R21") (pin "1") (pinfunction "1_1") (pintype "passive"))
      (node (ref "R38") (pin "2") (pinfunction "2_2") (pintype "passive"))
      (node (ref "T10") (pin "3") (pinfunction "D_3") (pintype "passive"))
    )
    (net (code "4") (name "-5_PUMP") (class "Default")
      (node (ref "C12") (pin "-") (pinfunction "-_-") (pintype "passive"))
      (node (ref "IC14") (pin "5") (pinfunction "-VIN_5") (pintype "input"))
      (node (ref "IC18") (pin "5") (pinfunction "VO_5") (pintype "output"))
      (node (ref "R4") (pin "1") (pinfunction "1_1") (pintype "passive"))
    )
    (net (code "5") (name "/~{CS_DAC}") (class "Default")
      (node (ref "IC5") (pin "2") (pinfunction "~{CS}_2") (pintype "input"))
      (node (ref "U1") (pin "31") (pinfunction "PD1_31") (pintype "bidirectional"))
    )
    (net (code "6") (name "/~{CS_GPS}") (class "Default")
      (node (ref "IC10") (pin "1") (pinfunction "~{OE}_1") (pintype "bidirectional"))
      (node (ref "IC11") (pin "1") (pinfunction "~{OE}_1") (pintype "bidirectional"))
      (node (ref "IC4") (pin "2") (pinfunction "SS_N_2") (pintype "output"))
      (node (ref "IC7") (pin "1") (pinfunction "~{OE}_1") (pintype "bidirectional"))
      (node (ref "U1") (pin "2") (pinfunction "PD4_2") (pintype "bidirectional"))
    )
    (net (code "7") (name "/~{LDAC}") (class "Default")
      (node (ref "IC5") (pin "5") (pinfunction "~{LDAC}_5") (pintype "input"))
      (node (ref "U1") (pin "32") (pinfunction "PD2_32") (pintype "bidirectional"))
    )
    (net (code "8") (name "2.48V") (class "Default")
      (node (ref "C25") (pin "2") (pinfunction "2_2") (pintype "passive"))
      (node (ref "IC16") (pin "2") (pinfunction "K_2") (pintype "bidirectional"))
      (node (ref "IC8") (pin "3") (pinfunction "+IN_3") (pintype "input"))
      (node (ref "R28") (pin "2") (pinfunction "2_2") (pintype "passive"))
      (node (ref "R59") (pin "2") (pinfunction "2_2") (pintype "passive"))
      (node (ref "R84") (pin "2") (pinfunction "2_2") (pintype "passive"))
      (node (ref "R85") (pin "1") (pinfunction "1_1") (pintype "passive"))
    )
    (net (code "9") (name "3V3_LDO_OFF") (class "Default")
      (node (ref "R55") (pin "1") (pinfunction "1_1") (pintype "passive"))
      (node (ref "T4") (pin "1") (pinfunction "G_1") (pintype "passive"))
      (node (ref "U1") (pin "14") (pinfunction "PB2_14") (pintype "bidirectional"))
    )
    (net (code "10") (name "5..15V") (class "Default")
      (node (ref "D8") (pin "A") (pinfunction "A_A") (pintype "passive"))
      (node (ref "J1") (pin "3") (pinfunction "3_3") (pintype "passive"))
    )
    (net (code "11") (name "144{slash}27") (class "Default")
      (node (ref "D3") (pin "C") (pinfunction "K_C") (pintype "passive"))
      (node (ref "IC3") (pin "6") (pinfunction "S_6") (pintype "power_in"))
      (node (ref "R100") (pin "1") (pinfunction "1_1") (pintype "passive"))
      (node (ref "R48") (pin "1") (pinfunction "1_1") (pintype "passive"))
      (node (ref "R64") (pin "2") (pinfunction "2_2") (pintype "passive"))
      (node (ref "R99") (pin "2") (pinfunction "2_2") (pintype "passive"))
      (node (ref "T11") (pin "1") (pinfunction "G_1") (pintype "passive"))
      (node (ref "T3") (pin "1") (pinfunction "G_1") (pintype "passive"))
    )
    (net (code "12") (name "144{slash}27_PROC") (class "Default")
      (node (ref "R100") (pin "2") (pinfunction "2_2") (pintype "passive"))
      (node (ref "U1") (pin "9") (pinfunction "PD5_9") (pintype "bidirectional"))
    )
    (net (code "13") (name "ANT_GPS") (class "Default")
      (node (ref "IC4") (pin "11") (pinfunction "RF_IN_11") (pintype "input"))
      (node (ref "L1") (pin "1") (pinfunction "1_1") (pintype "passive"))
    )
    (net (code "14") (name "ANT_OUT") (class "Default")
      (node (ref "C60") (pin "1") (pinfunction "1_1") (pintype "passive"))
      (node (ref "X1") (pin "1") (pinfunction "1_1") (pintype "passive"))
    )
    (net (code "15") (name "ANT_OUT1") (class "Default")
      (node (ref "C79") (pin "1") (pinfunction "1_1") (pintype "passive"))
      (node (ref "X3") (pin "1") (pinfunction "1_1") (pintype "passive"))
    )
    (net (code "16") (name "CORR_DAC") (class "Default")
      (node (ref "IC5") (pin "6") (pinfunction "VOUTB_6") (pintype "output"))
      (node (ref "R60") (pin "2") (pinfunction "2_2") (pintype "passive"))
    )
    (net (code "17") (name "DAC_LVL") (class "Default")
      (node (ref "IC5") (pin "8") (pinfunction "VOUTA_8") (pintype "output"))
      (node (ref "R58") (pin "2") (pinfunction "2_2") (pintype "passive"))
      (node (ref "R66") (pin "2") (pinfunction "2_2") (pintype "passive"))
      (node (ref "R76") (pin "1") (pinfunction "1_1") (pintype "passive"))
      (node (ref "R76") (pin "2") (pinfunction "2_2") (pintype "passive"))
    )
    (net (code "18") (name "GND") (class "Default")
      (node (ref "BAT1") (pin "-") (pinfunction "-_-") (pintype "power_in"))
      (node (ref "C1") (pin "-") (pinfunction "-_-") (pintype "passive"))
      (node (ref "C10") (pin "1") (pinfunction "1_1") (pintype "passive"))
      (node (ref "C11") (pin "1") (pinfunction "1_1") (pintype "passive"))
      (node (ref "C12") (pin "+") (pinfunction "+_+") (pintype "passive"))
      (node (ref "C14") (pin "-") (pinfunction "-_-") (pintype "passive"))
      (node (ref "C15") (pin "+") (pinfunction "+_+") (pintype "passive"))
      (node (ref "C17") (pin "1") (pinfunction "1_1") (pintype "passive"))
      (node (ref "C2") (pin "1") (pinfunction "1_1") (pintype "passive"))
      (node (ref "C20") (pin "1") (pinfunction "A_1") (pintype "passive"))
      (node (ref "C22") (pin "2") (pinfunction "2_2") (pintype "passive"))
      (node (ref "C24") (pin "-") (pinfunction "-_-") (pintype "passive"))
      (node (ref "C25") (pin "1") (pinfunction "1_1") (pintype "passive"))
      (node (ref "C27") (pin "2") (pinfunction "2_2") (pintype "passive"))
      (node (ref "C28") (pin "1") (pinfunction "1_1") (pintype "passive"))
      (node (ref "C3") (pin "1") (pinfunction "1_1") (pintype "passive"))
      (node (ref "C30") (pin "1") (pinfunction "1_1") (pintype "passive"))
      (node (ref "C31") (pin "1") (pinfunction "1_1") (pintype "passive"))
      (node (ref "C32") (pin "1") (pinfunction "1_1") (pintype "passive"))
      (node (ref "C33") (pin "1") (pinfunction "1_1") (pintype "passive"))
      (node (ref "C34") (pin "1") (pinfunction "1_1") (pintype "passive"))
      (node (ref "C35") (pin "1") (pinfunction "1_1") (pintype "passive"))
      (node (ref "C36") (pin "1") (pinfunction "1_1") (pintype "passive"))
      (node (ref "C37") (pin "1") (pinfunction "1_1") (pintype "passive"))
      (node (ref "C38") (pin "1") (pinfunction "1_1") (pintype "passive"))
      (node (ref "C39") (pin "1") (pinfunction "1_1") (pintype "passive"))
      (node (ref "C4") (pin "1") (pinfunction "1_1") (pintype "passive"))
      (node (ref "C40") (pin "1") (pinfunction "1_1") (pintype "passive"))
      (node (ref "C41") (pin "1") (pinfunction "1_1") (pintype "passive"))
      (node (ref "C42") (pin "1") (pinfunction "1_1") (pintype "passive"))
      (node (ref "C44") (pin "2") (pinfunction "2_2") (pintype "passive"))
      (node (ref "C45") (pin "2") (pinfunction "2_2") (pintype "passive"))
      (node (ref "C46") (pin "1") (pinfunction "1_1") (pintype "passive"))
      (node (ref "C47") (pin "-") (pinfunction "-_-") (pintype "passive"))
      (node (ref "C48") (pin "1") (pinfunction "1_1") (pintype "passive"))
      (node (ref "C49") (pin "2") (pinfunction "2_2") (pintype "passive"))
      (node (ref "C5") (pin "1") (pinfunction "1_1") (pintype "passive"))
      (node (ref "C50") (pin "-") (pinfunction "-_-") (pintype "passive"))
      (node (ref "C51") (pin "1") (pinfunction "1_1") (pintype "passive"))
      (node (ref "C52") (pin "1") (pinfunction "1_1") (pintype "passive"))
      (node (ref "C53") (pin "1") (pinfunction "1_1") (pintype "passive"))
      (node (ref "C54") (pin "1") (pinfunction "1_1") (pintype "passive"))
      (node (ref "C55") (pin "-") (pinfunction "-_-") (pintype "passive"))
      (node (ref "C56") (pin "2") (pinfunction "2_2") (pintype "passive"))
      (node (ref "C57") (pin "1") (pinfunction "1_1") (pintype "passive"))
      (node (ref "C58") (pin "2") (pinfunction "2_2") (pintype "passive"))
      (node (ref "C59") (pin "1") (pinfunction "1_1") (pintype "passive"))
      (node (ref "C63") (pin "1") (pinfunction "1_1") (pintype "passive"))
      (node (ref "C64") (pin "1") (pinfunction "1_1") (pintype "passive"))
      (node (ref "C65") (pin "1") (pinfunction "1_1") (pintype "passive"))
      (node (ref "C66") (pin "1") (pinfunction "1_1") (pintype "passive"))
      (node (ref "C67") (pin "1") (pinfunction "1_1") (pintype "passive"))
      (node (ref "C69") (pin "2") (pinfunction "2_2") (pintype "passive"))
      (node (ref "C70") (pin "2") (pinfunction "2_2") (pintype "passive"))
      (node (ref "C71") (pin "-") (pinfunction "-_-") (pintype "passive"))
      (node (ref "C72") (pin "1") (pinfunction "1_1") (pintype "passive"))
      (node (ref "C73") (pin "1") (pinfunction "1_1") (pintype "passive"))
      (node (ref "C74") (pin "-") (pinfunction "-_-") (pintype "passive"))
      (node (ref "C75") (pin "2") (pinfunction "2_2") (pintype "passive"))
      (node (ref "C76") (pin "1") (pinfunction "1_1") (pintype "passive"))
      (node (ref "C77") (pin "2") (pinfunction "2_2") (pintype "passive"))
      (node (ref "C78") (pin "1") (pinfunction "1_1") (pintype "passive"))
      (node (ref "C8") (pin "2") (pinfunction "2_2") (pintype "passive"))
      (node (ref "C9") (pin "1") (pinfunction "1_1") (pintype "passive"))
      (node (ref "D3") (pin "A") (pinfunction "A_A") (pintype "passive"))
      (node (ref "D6") (pin "A") (pinfunction "A_A") (pintype "passive"))
      (node (ref "D7") (pin "A") (pinfunction "A_A") (pintype "passive"))
      (node (ref "D9") (pin "A") (pinfunction "A_A") (pintype "passive"))
      (node (ref "IC1") (pin "3") (pinfunction "GND_3") (pintype "power_in"))
      (node (ref "IC10") (pin "3") (pinfunction "GND_3") (pintype "power_in"))
      (node (ref "IC11") (pin "3") (pinfunction "GND_3") (pintype "power_in"))
      (node (ref "IC12") (pin "5") (pinfunction "GND_5") (pintype "power_in"))
      (node (ref "IC12") (pin "6") (pinfunction "GND_6") (pintype "power_in"))
      (node (ref "IC12") (pin "7") (pinfunction "GND_7") (pintype "power_in"))
      (node (ref "IC12") (pin "8") (pinfunction "GND_8") (pintype "power_in"))
      (node (ref "IC13") (pin "2") (pinfunction "GND_2") (pintype "power_in"))
      (node (ref "IC14") (pin "2") (pinfunction "GND_2") (pintype "power_in"))
      (node (ref "IC16") (pin "3") (pinfunction "A_3") (pintype "bidirectional"))
      (node (ref "IC17") (pin "2") (pinfunction "GND_2") (pintype "power_in"))
      (node (ref "IC18") (pin "3") (pinfunction "GND_3") (pintype "power_in"))
      (node (ref "IC2") (pin "4") (pinfunction "GND_4") (pintype "power_in"))
      (node (ref "IC3") (pin "2") (pinfunction "GND_2") (pintype "power_in"))
      (node (ref "IC4") (pin "10") (pinfunction "GND_10") (pintype "power_in"))
      (node (ref "IC4") (pin "12") (pinfunction "GND_12") (pintype "power_in"))
      (node (ref "IC4") (pin "13") (pinfunction "GND_13") (pintype "power_in"))
      (node (ref "IC4") (pin "24") (pinfunction "GND_24") (pintype "power_in"))
      (node (ref "IC5") (pin "7") (pinfunction "VSS_7") (pintype "power_in"))
      (node (ref "IC6") (pin "2") (pinfunction "GND_2") (pintype "power_in"))
      (node (ref "IC7") (pin "3") (pinfunction "GND_3") (pintype "power_in"))
      (node (ref "J1") (pin "1") (pinfunction "1_1") (pintype "passive"))
      (node (ref "JP1") (pin "1") (pinfunction "1_1") (pintype "passive"))
      (node (ref "JP2") (pin "3") (pinfunction "3_3") (pintype "passive"))
      (node (ref "JP4") (pin "1") (pinfunction "1_1") (pintype "passive"))
      (node (ref "JP4") (pin "3") (pinfunction "3_3") (pintype "passive"))
      (node (ref "JP4") (pin "5") (pinfunction "5_5") (pintype "passive"))
      (node (ref "JP4") (pin "7") (pinfunction "7_7") (pintype "passive"))
      (node (ref "L1") (pin "2") (pinfunction "2_2") (pintype "passive"))
      (node (ref "L6") (pin "1") (pinfunction "1_1") (pintype "passive"))
      (node (ref "LED1") (pin "C") (pinfunction "C_C") (pintype "passive"))
      (node (ref "Q3") (pin "2") (pinfunction "2_2") (pintype "passive"))
      (node (ref "Q3") (pin "P$1") (pinfunction "2_P$1") (pintype "passive"))
      (node (ref "R104") (pin "2") (pinfunction "2_2") (pintype "passive"))
      (node (ref "R108") (pin "2") (pinfunction "2_2") (pintype "passive"))
      (node (ref "R12") (pin "2") (pinfunction "2_2") (pintype "passive"))
      (node (ref "R15") (pin "2") (pinfunction "2_2") (pintype "passive"))
      (node (ref "R16") (pin "2") (pinfunction "2_2") (pintype "passive"))
      (node (ref "R19") (pin "2") (pinfunction "2_2") (pintype "passive"))
      (node (ref "R20") (pin "2") (pinfunction "2_2") (pintype "passive"))
      (node (ref "R23") (pin "2") (pinfunction "2_2") (pintype "passive"))
      (node (ref "R27") (pin "1") (pinfunction "1_1") (pintype "passive"))
      (node (ref "R3") (pin "1") (pinfunction "1_1") (pintype "passive"))
      (node (ref "R31") (pin "2") (pinfunction "2_2") (pintype "passive"))
      (node (ref "R32") (pin "2") (pinfunction "2_2") (pintype "passive"))
      (node (ref "R33") (pin "2") (pinfunction "2_2") (pintype "passive"))
      (node (ref "R42") (pin "1") (pinfunction "1_1") (pintype "passive"))
      (node (ref "R45") (pin "1") (pinfunction "1_1") (pintype "passive"))
      (node (ref "R46") (pin "1") (pinfunction "1_1") (pintype "passive"))
      (node (ref "R47") (pin "1") (pinfunction "1_1") (pintype "passive"))
      (node (ref "R54") (pin "2") (pinfunction "2_2") (pintype "passive"))
      (node (ref "R55") (pin "2") (pinfunction "2_2") (pintype "passive"))
      (node (ref "R68") (pin "2") (pinfunction "2_2") (pintype "passive"))
      (node (ref "R7") (pin "2") (pinfunction "2_2") (pintype "passive"))
      (node (ref "R71") (pin "2") (pinfunction "2_2") (pintype "passive"))
      (node (ref "R8") (pin "2") (pinfunction "2_2") (pintype "passive"))
      (node (ref "R80") (pin "2") (pinfunction "2_2") (pintype "passive"))
      (node (ref "R81") (pin "1") (pinfunction "1_1") (pintype "passive"))
      (node (ref "R82") (pin "1") (pinfunction "1_1") (pintype "passive"))
      (node (ref "R88") (pin "1") (pinfunction "1_1") (pintype "passive"))
      (node (ref "R94") (pin "1") (pinfunction "1_1") (pintype "passive"))
      (node (ref "SUPERCAP") (pin "-") (pinfunction "-_-") (pintype "passive"))
      (node (ref "SW1") (pin "2") (pinfunction "2_2") (pintype "passive"))
      (node (ref "SW1") (pin "3") (pinfunction "3_3") (pintype "passive"))
      (node (ref "SW2") (pin "2") (pinfunction "2_2") (pintype "passive"))
      (node (ref "SW2") (pin "3") (pinfunction "3_3") (pintype "passive"))
      (node (ref "T14") (pin "2") (pinfunction "S_2") (pintype "passive"))
      (node (ref "T14") (pin "2@1") (pinfunction "S_2@1") (pintype "passive"))
      (node (ref "T15") (pin "2") (pinfunction "S_2") (pintype "passive"))
      (node (ref "T15") (pin "2@1") (pinfunction "S_2@1") (pintype "passive"))
      (node (ref "T3") (pin "2") (pinfunction "S_2") (pintype "passive"))
      (node (ref "T4") (pin "2") (pinfunction "S_2") (pintype "passive"))
      (node (ref "T9") (pin "2") (pinfunction "S_2") (pintype "passive"))
      (node (ref "U1") (pin "21") (pinfunction "GND_21") (pintype "passive"))
      (node (ref "U1") (pin "3") (pinfunction "GND_2_3") (pintype "passive"))
      (node (ref "U1") (pin "5") (pinfunction "GND_3_5") (pintype "passive"))
      (node (ref "X1") (pin "G@1") (pinfunction "2_G@1") (pintype "passive"))
      (node (ref "X1") (pin "G@2") (pinfunction "2_G@2") (pintype "passive"))
      (node (ref "X1") (pin "G@3") (pinfunction "2_G@3") (pintype "passive"))
      (node (ref "X1") (pin "G@4") (pinfunction "2_G@4") (pintype "passive"))
      (node (ref "X2") (pin "G") (pinfunction "GND_G") (pintype "passive"))
      (node (ref "X2") (pin "R") (pinfunction "R_R") (pintype "passive"))
      (node (ref "X3") (pin "G@1") (pinfunction "2_G@1") (pintype "passive"))
      (node (ref "X3") (pin "G@2") (pinfunction "2_G@2") (pintype "passive"))
      (node (ref "X3") (pin "G@3") (pinfunction "2_G@3") (pintype "passive"))
      (node (ref "X3") (pin "G@4") (pinfunction "2_G@4") (pintype "passive"))
    )
    (net (code "19") (name "ICS_PWR") (class "Default")
      (node (ref "IC1") (pin "2") (pinfunction "VDD_2") (pintype "input"))
      (node (ref "JP1") (pin "3") (pinfunction "3_3") (pintype "passive"))
      (node (ref "JP2") (pin "1") (pinfunction "1_1") (pintype "passive"))
      (node (ref "T7") (pin "3") (pinfunction "D_3") (pintype "passive"))
    )
    (net (code "20") (name "LINE_IN") (class "Default")
      (node (ref "C7") (pin "-") (pinfunction "-_-") (pintype "passive"))
      (node (ref "X2") (pin "L") (pinfunction "L_L") (pintype "passive"))
    )
    (net (code "21") (name "MIC") (class "Default")
      (node (ref "C62") (pin "2") (pinfunction "2_2") (pintype "passive"))
      (node (ref "IC8") (pin "1") (pinfunction "OUT_1") (pintype "output"))
      (node (ref "R51") (pin "2") (pinfunction "2_2") (pintype "passive"))
      (node (ref "R83") (pin "1") (pinfunction "1_1") (pintype "passive"))
    )
    (net (code "22") (name "MISC") (class "Default")
      (node (ref "U1") (pin "22") (pinfunction "ADC7_22") (pintype "input"))
      (node (ref "U1") (pin "23") (pinfunction "PC0_23") (pintype "bidirectional"))
      (node (ref "U1") (pin "24") (pinfunction "PC1_24") (pintype "bidirectional"))
      (node (ref "U1") (pin "25") (pinfunction "PC2_25") (pintype "bidirectional"))
      (node (ref "U1") (pin "26") (pinfunction "PC3_26") (pintype "bidirectional"))
    )
    (net (code "23") (name "MISO{slash}{slash}SDO") (class "Default")
      (node (ref "J102") (pin "1") (pinfunction "1_1") (pintype "passive"))
      (node (ref "J102") (pin "2") (pinfunction "2_2") (pintype "passive"))
      (node (ref "JP4") (pin "2") (pinfunction "2_2") (pintype "passive"))
      (node (ref "Q10") (pin "3") (pinfunction "D_3") (pintype "passive"))
      (node (ref "R63") (pin "1") (pinfunction "1_1") (pintype "passive"))
      (node (ref "U1") (pin "16") (pinfunction "PB4_16") (pintype "bidirectional"))
    )
    (net (code "24") (name "MOSI{slash}{slash}SDI") (class "Default")
      (node (ref "IC5") (pin "4") (pinfunction "SDI_4") (pintype "input"))
      (node (ref "IC7") (pin "2") (pinfunction "A_2") (pintype "bidirectional"))
      (node (ref "J101") (pin "1") (pinfunction "1_1") (pintype "passive"))
      (node (ref "J101") (pin "2") (pinfunction "2_2") (pintype "passive"))
      (node (ref "JP4") (pin "10") (pinfunction "10_10") (pintype "passive"))
      (node (ref "U1") (pin "15") (pinfunction "PB3_15") (pintype "bidirectional"))
    )
    (net (code "25") (name "Net-(BAT1-Pad+)") (class "Default")
      (node (ref "BAT1") (pin "+") (pinfunction "+_+") (pintype "power_in"))
      (node (ref "R96") (pin "2") (pinfunction "2_2") (pintype "passive"))
    )
    (net (code "26") (name "Net-(C6-A)") (class "Default")
      (node (ref "C6") (pin "1") (pinfunction "A_1") (pintype "passive"))
      (node (ref "L3") (pin "1") (pinfunction "1_1") (pintype "passive"))
      (node (ref "T1") (pin "C") (pinfunction "C_C") (pintype "passive"))
      (node (ref "T1") (pin "C@1") (pinfunction "C_C@1") (pintype "passive"))
    )
    (net (code "27") (name "Net-(C11-Pad2)") (class "Default")
      (node (ref "C11") (pin "2") (pinfunction "2_2") (pintype "passive"))
      (node (ref "C26") (pin "1") (pinfunction "1_1") (pintype "passive"))
      (node (ref "L14") (pin "2") (pinfunction "2_2") (pintype "passive"))
    )
    (net (code "28") (name "Net-(C16-Pad1)") (class "Default")
      (node (ref "C16") (pin "1") (pinfunction "1_1") (pintype "passive"))
      (node (ref "C17") (pin "2") (pinfunction "2_2") (pintype "passive"))
      (node (ref "R16") (pin "1") (pinfunction "1_1") (pintype "passive"))
      (node (ref "T1") (pin "E") (pinfunction "E_E") (pintype "passive"))
    )
    (net (code "29") (name "Net-(C16-Pad2)") (class "Default")
      (node (ref "C16") (pin "2") (pinfunction "2_2") (pintype "passive"))
      (node (ref "C18") (pin "1") (pinfunction "1_1") (pintype "passive"))
      (node (ref "R17") (pin "2") (pinfunction "2_2") (pintype "passive"))
      (node (ref "R8") (pin "1") (pinfunction "1_1") (pintype "passive"))
      (node (ref "T1") (pin "B") (pinfunction "B_B") (pintype "passive"))
    )
    (net (code "30") (name "Net-(C18-Pad2)") (class "Default")
      (node (ref "C18") (pin "2") (pinfunction "2_2") (pintype "passive"))
      (node (ref "L12") (pin "2") (pinfunction "2_2") (pintype "passive"))
      (node (ref "Q2") (pin "2") (pinfunction "2_2") (pintype "passive"))
    )
    (net (code "31") (name "Net-(C19-Pad1)") (class "Default")
      (node (ref "C19") (pin "1") (pinfunction "1_1") (pintype "passive"))
      (node (ref "R21") (pin "2") (pinfunction "2_2") (pintype "passive"))
      (node (ref "R7") (pin "1") (pinfunction "1_1") (pintype "passive"))
      (node (ref "T2") (pin "B") (pinfunction "B_B") (pintype "passive"))
    )
    (net (code "32") (name "Net-(C19-Pad2)") (class "Default")
      (node (ref "C19") (pin "2") (pinfunction "2_2") (pintype "passive"))
      (node (ref "R40") (pin "2") (pinfunction "2_2") (pintype "passive"))
    )
    (net (code "33") (name "Net-(C20-E)") (class "Default")
      (node (ref "C20") (pin "2") (pinfunction "E_2") (pintype "passive"))
      (node (ref "L6") (pin "2") (pinfunction "2_2") (pintype "passive"))
      (node (ref "R40") (pin "1") (pinfunction "1_1") (pintype "passive"))
      (node (ref "R9") (pin "1") (pinfunction "1_1") (pintype "passive"))
    )
    (net (code "34") (name "Net-(C21-Pad1)") (class "Default")
      (node (ref "C21") (pin "1") (pinfunction "1_1") (pintype "passive"))
      (node (ref "C22") (pin "1") (pinfunction "1_1") (pintype "passive"))
      (node (ref "R33") (pin "1") (pinfunction "1_1") (pintype "passive"))
      (node (ref "R35") (pin "2") (pinfunction "2_2") (pintype "passive"))
      (node (ref "T6") (pin "B") (pinfunction "B_B") (pintype "passive"))
    )
    (net (code "35") (name "Net-(C21-Pad2)") (class "Default")
      (node (ref "C21") (pin "2") (pinfunction "2_2") (pintype "passive"))
      (node (ref "R9") (pin "2") (pinfunction "2_2") (pintype "passive"))
    )
    (net (code "36") (name "Net-(C23-Pad2)") (class "Default")
      (node (ref "C23") (pin "2") (pinfunction "2_2") (pintype "passive"))
      (node (ref "R13") (pin "1") (pinfunction "1_1") (pintype "passive"))
      (node (ref "R14") (pin "2") (pinfunction "2_2") (pintype "passive"))
    )
    (net (code "37") (name "Net-(C27-Pad1)") (class "Default")
      (node (ref "C27") (pin "1") (pinfunction "1_1") (pintype "passive"))
      (node (ref "R102") (pin "2") (pinfunction "2_2") (pintype "passive"))
      (node (ref "R97") (pin "1") (pinfunction "1_1") (pintype "passive"))
    )
    (net (code "38") (name "Net-(C28-Pad2)") (class "Default")
      (node (ref "C28") (pin "2") (pinfunction "2_2") (pintype "passive"))
      (node (ref "R23") (pin "1") (pinfunction "1_1") (pintype "passive"))
      (node (ref "T2") (pin "E") (pinfunction "E_E") (pintype "passive"))
    )
    (net (code "39") (name "Net-(C29-A)") (class "Default")
      (node (ref "C29") (pin "1") (pinfunction "A_1") (pintype "passive"))
      (node (ref "C53") (pin "2") (pinfunction "2_2") (pintype "passive"))
      (node (ref "C54") (pin "2") (pinfunction "2_2") (pintype "passive"))
      (node (ref "L10") (pin "2") (pinfunction "2_2") (pintype "passive"))
      (node (ref "L2") (pin "2") (pinfunction "2_2") (pintype "passive"))
      (node (ref "R10") (pin "1") (pinfunction "1_1") (pintype "passive"))
      (node (ref "R43") (pin "2") (pinfunction "2_2") (pintype "passive"))
    )
    (net (code "40") (name "Net-(C30-Pad2)") (class "Default")
      (node (ref "C30") (pin "2") (pinfunction "2_2") (pintype "passive"))
      (node (ref "C33") (pin "2") (pinfunction "2_2") (pintype "passive"))
      (node (ref "L2") (pin "1") (pinfunction "1_1") (pintype "passive"))
      (node (ref "L7") (pin "2") (pinfunction "2_2") (pintype "passive"))
    )
    (net (code "41") (name "Net-(C39-Pad2)") (class "Default")
      (node (ref "C39") (pin "2") (pinfunction "2_2") (pintype "passive"))
      (node (ref "C40") (pin "2") (pinfunction "2_2") (pintype "passive"))
      (node (ref "C42") (pin "2") (pinfunction "2_2") (pintype "passive"))
      (node (ref "L11") (pin "1") (pinfunction "1_1") (pintype "passive"))
      (node (ref "L8") (pin "2") (pinfunction "2_2") (pintype "passive"))
    )
    (net (code "42") (name "Net-(C43-Pad1)") (class "Default")
      (node (ref "C43") (pin "1") (pinfunction "1_1") (pintype "passive"))
      (node (ref "R11") (pin "2") (pinfunction "2_2") (pintype "passive"))
      (node (ref "R32") (pin "1") (pinfunction "1_1") (pintype "passive"))
    )
    (net (code "43") (name "Net-(C43-Pad2)") (class "Default")
      (node (ref "C43") (pin "2") (pinfunction "2_2") (pintype "passive"))
      (node (ref "R11") (pin "1") (pinfunction "1_1") (pintype "passive"))
      (node (ref "T6") (pin "E") (pinfunction "E_E") (pintype "passive"))
    )
    (net (code "44") (name "Net-(C44-Pad1)") (class "Default")
      (node (ref "C44") (pin "1") (pinfunction "1_1") (pintype "passive"))
      (node (ref "R34") (pin "2") (pinfunction "2_2") (pintype "passive"))
      (node (ref "R35") (pin "1") (pinfunction "1_1") (pintype "passive"))
      (node (ref "T5") (pin "B") (pinfunction "B_B") (pintype "passive"))
    )
    (net (code "45") (name "Net-(C45-Pad1)") (class "Default")
      (node (ref "C45") (pin "1") (pinfunction "1_1") (pintype "passive"))
      (node (ref "C50") (pin "+") (pinfunction "+_+") (pintype "passive"))
      (node (ref "R102") (pin "1") (pinfunction "1_1") (pintype "passive"))
      (node (ref "R103") (pin "2") (pinfunction "2_2") (pintype "passive"))
      (node (ref "R104") (pin "1") (pinfunction "1_1") (pintype "passive"))
    )
    (net (code "46") (name "Net-(C57-Pad2)") (class "Default")
      (node (ref "C57") (pin "2") (pinfunction "2_2") (pintype "passive"))
      (node (ref "L16") (pin "2") (pinfunction "2_2") (pintype "passive"))
      (node (ref "L17") (pin "1") (pinfunction "1_1") (pintype "passive"))
    )
    (net (code "47") (name "Net-(C58-Pad1)") (class "Default")
      (node (ref "C58") (pin "1") (pinfunction "1_1") (pintype "passive"))
      (node (ref "C59") (pin "2") (pinfunction "2_2") (pintype "passive"))
      (node (ref "C60") (pin "2") (pinfunction "2_2") (pintype "passive"))
      (node (ref "L17") (pin "2") (pinfunction "2_2") (pintype "passive"))
    )
    (net (code "48") (name "Net-(C61-Pad1)") (class "Default")
      (node (ref "C61") (pin "1") (pinfunction "1_1") (pintype "passive"))
      (node (ref "M1") (pin "2") (pinfunction "2_2") (pintype "passive"))
      (node (ref "R79") (pin "2") (pinfunction "2_2") (pintype "passive"))
    )
    (net (code "49") (name "Net-(C67-Pad2)") (class "Default")
      (node (ref "C67") (pin "2") (pinfunction "2_2") (pintype "passive"))
      (node (ref "C68") (pin "1") (pinfunction "1_1") (pintype "passive"))
      (node (ref "L18") (pin "2") (pinfunction "2_2") (pintype "passive"))
    )
    (net (code "50") (name "Net-(C69-Pad1)") (class "Default")
      (node (ref "C69") (pin "1") (pinfunction "1_1") (pintype "passive"))
      (node (ref "R105") (pin "1") (pinfunction "1_1") (pintype "passive"))
      (node (ref "R106") (pin "2") (pinfunction "2_2") (pintype "passive"))
    )
    (net (code "51") (name "Net-(C70-Pad1)") (class "Default")
      (node (ref "C70") (pin "1") (pinfunction "1_1") (pintype "passive"))
      (node (ref "C71") (pin "+") (pinfunction "+_+") (pintype "passive"))
      (node (ref "R106") (pin "1") (pinfunction "1_1") (pintype "passive"))
      (node (ref "R107") (pin "2") (pinfunction "2_2") (pintype "passive"))
      (node (ref "R108") (pin "1") (pinfunction "1_1") (pintype "passive"))
    )
    (net (code "52") (name "Net-(C76-Pad2)") (class "Default")
      (node (ref "C76") (pin "2") (pinfunction "2_2") (pintype "passive"))
      (node (ref "L20") (pin "2") (pinfunction "2_2") (pintype "passive"))
      (node (ref "L21") (pin "1") (pinfunction "1_1") (pintype "passive"))
    )
    (net (code "53") (name "Net-(C77-Pad1)") (class "Default")
      (node (ref "C77") (pin "1") (pinfunction "1_1") (pintype "passive"))
      (node (ref "C78") (pin "2") (pinfunction "2_2") (pintype "passive"))
      (node (ref "C79") (pin "2") (pinfunction "2_2") (pintype "passive"))
      (node (ref "L21") (pin "2") (pinfunction "2_2") (pintype "passive"))
    )
    (net (code "54") (name "Net-(D1-A1)") (class "Default")
      (node (ref "D1") (pin "1") (pinfunction "A1_1") (pintype "passive"))
      (node (ref "D2") (pin "1") (pinfunction "A1_1") (pintype "passive"))
      (node (ref "L9") (pin "2") (pinfunction "2_2") (pintype "passive"))
      (node (ref "Q2") (pin "1") (pinfunction "1_1") (pintype "passive"))
      (node (ref "R20") (pin "1") (pinfunction "1_1") (pintype "passive"))
    )
    (net (code "55") (name "Net-(D1-A2)") (class "Default")
      (node (ref "D1") (pin "2") (pinfunction "A2_2") (pintype "passive"))
      (node (ref "D2") (pin "2") (pinfunction "A2_2") (pintype "passive"))
      (node (ref "Q3") (pin "1") (pinfunction "1_1") (pintype "passive"))
      (node (ref "R19") (pin "1") (pinfunction "1_1") (pintype "passive"))
    )
    (net (code "56") (name "Net-(D1-K)") (class "Default")
      (node (ref "D1") (pin "3") (pinfunction "K_3") (pintype "bidirectional"))
      (node (ref "D2") (pin "3") (pinfunction "K_3") (pintype "bidirectional"))
      (node (ref "L4") (pin "2") (pinfunction "2_2") (pintype "passive"))
    )
    (net (code "57") (name "Net-(D4-K)") (class "Default")
      (node (ref "C1") (pin "+") (pinfunction "+_+") (pintype "passive"))
      (node (ref "D4") (pin "C") (pinfunction "K_C") (pintype "passive"))
      (node (ref "F3") (pin "P$2") (pinfunction "2_P$2") (pintype "passive"))
      (node (ref "F4") (pin "P$1") (pinfunction "1_P$1") (pintype "passive"))
      (node (ref "IC12") (pin "1") (pinfunction "EN_1") (pintype "input"))
      (node (ref "IC12") (pin "2") (pinfunction "VIN_2") (pintype "input"))
    )
    (net (code "58") (name "Net-(D7-K)") (class "Default")
      (node (ref "D7") (pin "C") (pinfunction "K_C") (pintype "passive"))
      (node (ref "IC1") (pin "1") (pinfunction "X1/ICLK_1") (pintype "input"))
      (node (ref "R5") (pin "2") (pinfunction "2_2") (pintype "passive"))
      (node (ref "R71") (pin "1") (pinfunction "1_1") (pintype "passive"))
    )
    (net (code "59") (name "Net-(D8-K)") (class "Default")
      (node (ref "D8") (pin "C") (pinfunction "K_C") (pintype "passive"))
      (node (ref "F3") (pin "P$1") (pinfunction "1_P$1") (pintype "passive"))
      (node (ref "F4") (pin "P$2") (pinfunction "2_P$2") (pintype "passive"))
    )
    (net (code "60") (name "Net-(D9-K)") (class "Default")
      (node (ref "C7") (pin "+") (pinfunction "+_+") (pintype "passive"))
      (node (ref "D5") (pin "A") (pinfunction "A_A") (pintype "passive"))
      (node (ref "D9") (pin "C") (pinfunction "K_C") (pintype "passive"))
      (node (ref "IC6") (pin "1") (pinfunction "B2_1") (pintype "power_in"))
      (node (ref "R51") (pin "1") (pinfunction "1_1") (pintype "passive"))
    )
    (net (code "61") (name "Net-(F1-1)") (class "Default")
      (node (ref "F1") (pin "P$1") (pinfunction "1_P$1") (pintype "passive"))
      (node (ref "IC13") (pin "5") (pinfunction "VO_5") (pintype "output"))
    )
    (net (code "62") (name "Net-(IC1-CLK)") (class "Default")
      (node (ref "IC1") (pin "5") (pinfunction "CLK_5") (pintype "passive"))
      (node (ref "R18") (pin "2") (pinfunction "2_2") (pintype "passive"))
    )
    (net (code "63") (name "Net-(IC1-OE)") (class "Default")
      (node (ref "IC1") (pin "7") (pinfunction "OE_7") (pintype "passive"))
      (node (ref "T3") (pin "3") (pinfunction "D_3") (pintype "passive"))
    )
    (net (code "64") (name "Net-(IC1-X2)") (class "Default")
      (node (ref "IC1") (pin "8") (pinfunction "X2_8") (pintype "output"))
      (node (ref "R42") (pin "2") (pinfunction "2_2") (pintype "passive"))
    )
    (net (code "65") (name "Net-(IC2-A0)") (class "Default")
      (node (ref "IC2") (pin "7") (pinfunction "A0_7") (pintype "passive"))
      (node (ref "R45") (pin "2") (pinfunction "2_2") (pintype "passive"))
    )
    (net (code "66") (name "Net-(IC2-A1)") (class "Default")
      (node (ref "IC2") (pin "6") (pinfunction "A1_6") (pintype "passive"))
      (node (ref "R46") (pin "2") (pinfunction "2_2") (pintype "passive"))
    )
    (net (code "67") (name "Net-(IC2-A2)") (class "Default")
      (node (ref "IC2") (pin "5") (pinfunction "A2_5") (pintype "passive"))
      (node (ref "R47") (pin "2") (pinfunction "2_2") (pintype "passive"))
    )
    (net (code "68") (name "Net-(IC3-A)") (class "Default")
      (node (ref "C31") (pin "2") (pinfunction "2_2") (pintype "passive"))
      (node (ref "C32") (pin "2") (pinfunction "2_2") (pintype "passive"))
      (node (ref "IC3") (pin "4") (pinfunction "A_4") (pintype "input"))
      (node (ref "L7") (pin "1") (pinfunction "1_1") (pintype "passive"))
    )
    (net (code "69") (name "Net-(IC3-B1)") (class "Default")
      (node (ref "IC3") (pin "3") (pinfunction "B1_3") (pintype "power_in"))
      (node (ref "R5") (pin "1") (pinfunction "1_1") (pintype "passive"))
    )
    (net (code "70") (name "Net-(IC4-EXTINT0)") (class "Default")
      (node (ref "IC4") (pin "4") (pinfunction "EXTINT0_4") (pintype "input"))
      (node (ref "R73") (pin "2") (pinfunction "2_2") (pintype "passive"))
    )
    (net (code "71") (name "Net-(IC4-MOSI{slash}CFG_COM0)") (class "Default")
      (node (ref "IC4") (pin "14") (pinfunction "MOSI/CFG_COM0_14") (pintype "input"))
      (node (ref "IC7") (pin "4") (pinfunction "Y_4") (pintype "bidirectional"))
    )
    (net (code "72") (name "Net-(IC4-R1)") (class "Default")
      (node (ref "IC4") (pin "8") (pinfunction "R1_8") (pintype "bidirectional"))
      (node (ref "IC4") (pin "9") (pinfunction "VCC_RF_9") (pintype "input"))
    )
    (net (code "73") (name "Net-(IC4-RXD1)") (class "Default")
      (node (ref "IC4") (pin "21") (pinfunction "RXD1_21") (pintype "input"))
      (node (ref "R90") (pin "2") (pinfunction "2_2") (pintype "passive"))
    )
    (net (code "74") (name "Net-(IC4-SCL2)") (class "Default")
      (node (ref "IC4") (pin "19") (pinfunction "SCL2_19") (pintype "input"))
      (node (ref "R92") (pin "2") (pinfunction "2_2") (pintype "passive"))
    )
    (net (code "75") (name "Net-(IC4-SDA2)") (class "Default")
      (node (ref "IC4") (pin "18") (pinfunction "SDA2_18") (pintype "input"))
      (node (ref "R91") (pin "2") (pinfunction "2_2") (pintype "passive"))
    )
    (net (code "76") (name "Net-(IC4-TIMEPULSE)") (class "Default")
      (node (ref "IC4") (pin "3") (pinfunction "TIMEPULSE_3") (pintype "output"))
      (node (ref "R77") (pin "2") (pinfunction "2_2") (pintype "passive"))
    )
    (net (code "77") (name "Net-(IC4-TXD1)") (class "Default")
      (node (ref "IC4") (pin "20") (pinfunction "TXD1_20") (pintype "input"))
      (node (ref "R89") (pin "2") (pinfunction "2_2") (pintype "passive"))
    )
    (net (code "78") (name "Net-(IC4-USB_DM)") (class "Default")
      (node (ref "IC4") (pin "5") (pinfunction "USB_DM_5") (pintype "input"))
      (node (ref "R86") (pin "2") (pinfunction "2_2") (pintype "passive"))
    )
    (net (code "79") (name "Net-(IC4-USB_DP)") (class "Default")
      (node (ref "IC4") (pin "6") (pinfunction "USB_DP_6") (pintype "input"))
      (node (ref "R87") (pin "2") (pinfunction "2_2") (pintype "passive"))
    )
    (net (code "80") (name "Net-(IC4-VDDUSB)") (class "Default")
      (node (ref "IC4") (pin "7") (pinfunction "VDDUSB_7") (pintype "input"))
      (node (ref "R88") (pin "2") (pinfunction "2_2") (pintype "passive"))
    )
    (net (code "81") (name "Net-(IC4-V_BCKP)") (class "Default")
      (node (ref "IC4") (pin "22") (pinfunction "V_BCKP_22") (pintype "power_in"))
      (node (ref "R96") (pin "1") (pinfunction "1_1") (pintype "passive"))
      (node (ref "SUPERCAP") (pin "+") (pinfunction "+_+") (pintype "passive"))
      (node (ref "T12") (pin "2") (pinfunction "E_2") (pintype "passive"))
    )
    (net (code "82") (name "Net-(IC6-A)") (class "Default")
      (node (ref "IC6") (pin "4") (pinfunction "A_4") (pintype "input"))
      (node (ref "R25") (pin "2") (pinfunction "2_2") (pintype "passive"))
    )
    (net (code "83") (name "Net-(IC6-B1)") (class "Default")
      (node (ref "IC6") (pin "3") (pinfunction "B1_3") (pintype "power_in"))
      (node (ref "R75") (pin "1") (pinfunction "1_1") (pintype "passive"))
    )
    (net (code "84") (name "Net-(IC8A--IN)") (class "Default")
      (node (ref "C61") (pin "2") (pinfunction "2_2") (pintype "passive"))
      (node (ref "C62") (pin "1") (pinfunction "1_1") (pintype "passive"))
      (node (ref "IC8") (pin "2") (pinfunction "-IN_2") (pintype "input"))
      (node (ref "R78") (pin "1") (pinfunction "1_1") (pintype "passive"))
    )
    (net (code "85") (name "Net-(IC8B-+IN)") (class "Default")
      (node (ref "IC8") (pin "5") (pinfunction "+IN_5") (pintype "input"))
      (node (ref "R50") (pin "1") (pinfunction "1_1") (pintype "passive"))
      (node (ref "R52") (pin "1") (pinfunction "1_1") (pintype "passive"))
      (node (ref "R58") (pin "1") (pinfunction "1_1") (pintype "passive"))
      (node (ref "R66") (pin "1") (pinfunction "1_1") (pintype "passive"))
    )
    (net (code "86") (name "Net-(IC8B--IN)") (class "Default")
      (node (ref "IC8") (pin "6") (pinfunction "-IN_6") (pintype "input"))
      (node (ref "R26") (pin "2") (pinfunction "2_2") (pintype "passive"))
      (node (ref "R49") (pin "2") (pinfunction "2_2") (pintype "passive"))
      (node (ref "R54") (pin "1") (pinfunction "1_1") (pintype "passive"))
    )
    (net (code "87") (name "Net-(IC8B-OUT)") (class "Default")
      (node (ref "IC8") (pin "7") (pinfunction "OUT_7") (pintype "output"))
      (node (ref "R26") (pin "1") (pinfunction "1_1") (pintype "passive"))
      (node (ref "R49") (pin "1") (pinfunction "1_1") (pintype "passive"))
      (node (ref "R75") (pin "2") (pinfunction "2_2") (pintype "passive"))
    )
    (net (code "88") (name "Net-(IC9A-+IN)") (class "Default")
      (node (ref "IC9") (pin "3") (pinfunction "+IN_3") (pintype "input"))
      (node (ref "R25") (pin "1") (pinfunction "1_1") (pintype "passive"))
      (node (ref "R27") (pin "2") (pinfunction "2_2") (pintype "passive"))
    )
    (net (code "89") (name "Net-(IC9A--IN)") (class "Default")
      (node (ref "IC9") (pin "2") (pinfunction "-IN_2") (pintype "input"))
      (node (ref "R28") (pin "1") (pinfunction "1_1") (pintype "passive"))
      (node (ref "R29") (pin "2") (pinfunction "2_2") (pintype "passive"))
    )
    (net (code "90") (name "Net-(IC9A-OUT)") (class "Default")
      (node (ref "IC9") (pin "1") (pinfunction "OUT_1") (pintype "output"))
      (node (ref "R13") (pin "2") (pinfunction "2_2") (pintype "passive"))
      (node (ref "R29") (pin "1") (pinfunction "1_1") (pintype "passive"))
    )
    (net (code "91") (name "Net-(IC9B-+IN)") (class "Default")
      (node (ref "C8") (pin "1") (pinfunction "1_1") (pintype "passive"))
      (node (ref "IC9") (pin "5") (pinfunction "+IN_5") (pintype "input"))
      (node (ref "R14") (pin "1") (pinfunction "1_1") (pintype "passive"))
    )
    (net (code "92") (name "Net-(IC9B--IN)") (class "Default")
      (node (ref "IC9") (pin "6") (pinfunction "-IN_6") (pintype "input"))
      (node (ref "R15") (pin "1") (pinfunction "1_1") (pintype "passive"))
      (node (ref "R22") (pin "2") (pinfunction "2_2") (pintype "passive"))
      (node (ref "R24") (pin "2") (pinfunction "2_2") (pintype "passive"))
    )
    (net (code "93") (name "Net-(IC9B-OUT)") (class "Default")
      (node (ref "C23") (pin "1") (pinfunction "1_1") (pintype "passive"))
      (node (ref "IC9") (pin "7") (pinfunction "OUT_7") (pintype "output"))
      (node (ref "R22") (pin "1") (pinfunction "1_1") (pintype "passive"))
      (node (ref "R24") (pin "1") (pinfunction "1_1") (pintype "passive"))
      (node (ref "R30") (pin "2") (pinfunction "2_2") (pintype "passive"))
    )
    (net (code "94") (name "Net-(IC10A-Y)") (class "Default")
      (node (ref "IC10") (pin "4") (pinfunction "Y_4") (pintype "bidirectional"))
      (node (ref "IC4") (pin "16") (pinfunction "SCK/CFG_GPS0_16") (pintype "input"))
      (node (ref "J105") (pin "1") (pinfunction "1_1") (pintype "passive"))
      (node (ref "J105") (pin "2") (pinfunction "2_2") (pintype "passive"))
    )
    (net (code "95") (name "Net-(IC11A-A)") (class "Default")
      (node (ref "IC11") (pin "2") (pinfunction "A_2") (pintype "bidirectional"))
      (node (ref "IC4") (pin "15") (pinfunction "MISO/CFG_COM1_15") (pintype "input"))
      (node (ref "R74") (pin "1") (pinfunction "1_1") (pintype "passive"))
      (node (ref "R74") (pin "2") (pinfunction "2_2") (pintype "passive"))
    )
    (net (code "96") (name "Net-(IC11A-Y)") (class "Default")
      (node (ref "IC11") (pin "4") (pinfunction "Y_4") (pintype "bidirectional"))
      (node (ref "Q10") (pin "2") (pinfunction "S_2") (pintype "passive"))
      (node (ref "R6") (pin "2") (pinfunction "2_2") (pintype "passive"))
    )
    (net (code "97") (name "Net-(IC12-ADJ)") (class "Default")
      (node (ref "C41") (pin "2") (pinfunction "2_2") (pintype "passive"))
      (node (ref "IC12") (pin "4") (pinfunction "ADJ_4") (pintype "passive"))
      (node (ref "R80") (pin "1") (pinfunction "1_1") (pintype "passive"))
      (node (ref "R95") (pin "2") (pinfunction "2_2") (pintype "passive"))
    )
    (net (code "98") (name "Net-(IC13-EN)") (class "Default")
      (node (ref "IC13") (pin "3") (pinfunction "EN_3") (pintype "input"))
      (node (ref "R1") (pin "2") (pinfunction "2_2") (pintype "passive"))
      (node (ref "T4") (pin "3") (pinfunction "D_3") (pintype "passive"))
    )
    (net (code "99") (name "Net-(IC14-ADJ)") (class "Default")
      (node (ref "IC14") (pin "3") (pinfunction "ADJ_3") (pintype "passive"))
      (node (ref "R2") (pin "2") (pinfunction "2_2") (pintype "passive"))
      (node (ref "R3") (pin "2") (pinfunction "2_2") (pintype "passive"))
    )
    (net (code "100") (name "Net-(IC14-EN)") (class "Default")
      (node (ref "IC14") (pin "1") (pinfunction "EN_1") (pintype "input"))
      (node (ref "R4") (pin "2") (pinfunction "2_2") (pintype "passive"))
    )
    (net (code "101") (name "Net-(IC15A-+IN)") (class "Default")
      (node (ref "IC15") (pin "3") (pinfunction "+IN_3") (pintype "input"))
      (node (ref "R31") (pin "1") (pinfunction "1_1") (pintype "passive"))
    )
    (net (code "102") (name "Net-(IC15A--IN)") (class "Default")
      (node (ref "IC15") (pin "2") (pinfunction "-IN_2") (pintype "input"))
      (node (ref "IC17") (pin "4") (pinfunction "A_4") (pintype "input"))
      (node (ref "R30") (pin "1") (pinfunction "1_1") (pintype "passive"))
      (node (ref "R62") (pin "1") (pinfunction "1_1") (pintype "passive"))
      (node (ref "R62") (pin "2") (pinfunction "2_2") (pintype "passive"))
    )
    (net (code "103") (name "Net-(IC15A-OUT)") (class "Default")
      (node (ref "IC15") (pin "1") (pinfunction "OUT_1") (pintype "output"))
      (node (ref "R37") (pin "2") (pinfunction "2_2") (pintype "passive"))
      (node (ref "R39") (pin "2") (pinfunction "2_2") (pintype "passive"))
      (node (ref "R41") (pin "2") (pinfunction "2_2") (pintype "passive"))
      (node (ref "R44") (pin "1") (pinfunction "1_1") (pintype "passive"))
      (node (ref "R61") (pin "2") (pinfunction "2_2") (pintype "passive"))
    )
    (net (code "104") (name "Net-(IC15B-+IN)") (class "Default")
      (node (ref "IC15") (pin "5") (pinfunction "+IN_5") (pintype "input"))
      (node (ref "R59") (pin "1") (pinfunction "1_1") (pintype "passive"))
      (node (ref "R60") (pin "1") (pinfunction "1_1") (pintype "passive"))
      (node (ref "R61") (pin "1") (pinfunction "1_1") (pintype "passive"))
    )
    (net (code "105") (name "Net-(IC15B--IN)") (class "Default")
      (node (ref "C63") (pin "2") (pinfunction "2_2") (pintype "passive"))
      (node (ref "IC15") (pin "6") (pinfunction "-IN_6") (pintype "input"))
      (node (ref "R68") (pin "1") (pinfunction "1_1") (pintype "passive"))
      (node (ref "R69") (pin "1") (pinfunction "1_1") (pintype "passive"))
    )
    (net (code "106") (name "Net-(IC16-R)") (class "Default")
      (node (ref "IC16") (pin "1") (pinfunction "R_1") (pintype "bidirectional"))
      (node (ref "R82") (pin "2") (pinfunction "2_2") (pintype "passive"))
      (node (ref "R84") (pin "1") (pinfunction "1_1") (pintype "passive"))
    )
    (net (code "107") (name "Net-(IC17-B1)") (class "Default")
      (node (ref "IC17") (pin "3") (pinfunction "B1_3") (pintype "power_in"))
      (node (ref "R39") (pin "1") (pinfunction "1_1") (pintype "passive"))
      (node (ref "R41") (pin "1") (pinfunction "1_1") (pintype "passive"))
    )
    (net (code "108") (name "Net-(IC17-B2)") (class "Default")
      (node (ref "IC17") (pin "1") (pinfunction "B2_1") (pintype "power_in"))
      (node (ref "R37") (pin "1") (pinfunction "1_1") (pintype "passive"))
      (node (ref "R44") (pin "2") (pinfunction "2_2") (pintype "passive"))
    )
    (net (code "109") (name "Net-(IC18-+CAP)") (class "Default")
      (node (ref "C13") (pin "+") (pinfunction "+_+") (pintype "passive"))
      (node (ref "IC18") (pin "2") (pinfunction "+CAP_2") (pintype "input"))
    )
    (net (code "110") (name "Net-(IC18--CAP)") (class "Default")
      (node (ref "C13") (pin "-") (pinfunction "-_-") (pintype "passive"))
      (node (ref "IC18") (pin "4") (pinfunction "-CAP_4") (pintype "power_in"))
    )
    (net (code "111") (name "Net-(L12-Pad1)") (class "Default")
      (node (ref "L12") (pin "1") (pinfunction "1_1") (pintype "passive"))
      (node (ref "L9") (pin "1") (pinfunction "1_1") (pintype "passive"))
    )
    (net (code "112") (name "Net-(LED1-PadA)") (class "Default")
      (node (ref "LED1") (pin "A") (pinfunction "A_A") (pintype "passive"))
      (node (ref "R53") (pin "1") (pinfunction "1_1") (pintype "passive"))
    )
    (net (code "113") (name "Net-(R10-Pad2)") (class "Default")
      (node (ref "R10") (pin "2") (pinfunction "2_2") (pintype "passive"))
      (node (ref "R36") (pin "2") (pinfunction "2_2") (pintype "passive"))
      (node (ref "T5") (pin "C") (pinfunction "C_C") (pintype "passive"))
      (node (ref "T5") (pin "C@1") (pinfunction "C_C@1") (pintype "passive"))
    )
    (net (code "114") (name "Net-(R34-Pad1)") (class "Default")
      (node (ref "R34") (pin "1") (pinfunction "1_1") (pintype "passive"))
      (node (ref "R36") (pin "1") (pinfunction "1_1") (pintype "passive"))
      (node (ref "R38") (pin "1") (pinfunction "1_1") (pintype "passive"))
    )
    (net (code "115") (name "Net-(R43-Pad1)") (class "Default")
      (node (ref "R43") (pin "1") (pinfunction "1_1") (pintype "passive"))
      (node (ref "T2") (pin "C") (pinfunction "C_C") (pintype "passive"))
      (node (ref "T2") (pin "C@1") (pinfunction "C_C@1") (pintype "passive"))
    )
    (net (code "116") (name "Net-(R78-Pad2)") (class "Default")
      (node (ref "R78") (pin "2") (pinfunction "2_2") (pintype "passive"))
      (node (ref "R83") (pin "2") (pinfunction "2_2") (pintype "passive"))
    )
    (net (code "117") (name "Net-(R99-Pad1)") (class "Default")
      (node (ref "R99") (pin "1") (pinfunction "1_1") (pintype "passive"))
      (node (ref "SW1") (pin "1") (pinfunction "1_1") (pintype "passive"))
    )
    (net (code "118") (name "Net-(R120-Pad1)") (class "Default")
      (node (ref "R120") (pin "1") (pinfunction "1_1") (pintype "passive"))
      (node (ref "SW2") (pin "1") (pinfunction "1_1") (pintype "passive"))
    )
    (net (code "119") (name "Net-(T5-PadE)") (class "Default")
      (node (ref "T5") (pin "E") (pinfunction "E_E") (pintype "passive"))
      (node (ref "T6") (pin "C") (pinfunction "C_C") (pintype "passive"))
      (node (ref "T6") (pin "C@1") (pinfunction "C_C@1") (pintype "passive"))
    )
    (net (code "120") (name "Net-(T7-S)") (class "Default")
      (node (ref "L13") (pin "1") (pinfunction "1_1") (pintype "passive"))
      (node (ref "T7") (pin "2") (pinfunction "S_2") (pintype "passive"))
    )
    (net (code "121") (name "Net-(T8-G)") (class "Default")
      (node (ref "R67") (pin "2") (pinfunction "2_2") (pintype "passive"))
      (node (ref "T8") (pin "1") (pinfunction "G_1") (pintype "passive"))
      (node (ref "T9") (pin "3") (pinfunction "D_3") (pintype "passive"))
    )
    (net (code "122") (name "Net-(T10-S)") (class "Default")
      (node (ref "L5") (pin "1") (pinfunction "1_1") (pintype "passive"))
      (node (ref "T10") (pin "2") (pinfunction "S_2") (pintype "passive"))
    )
    (net (code "123") (name "Net-(T11-D)") (class "Default")
      (node (ref "M1") (pin "1") (pinfunction "1_1") (pintype "passive"))
      (node (ref "T11") (pin "3") (pinfunction "D_3") (pintype "passive"))
    )
    (net (code "124") (name "Net-(T12-B)") (class "Default")
      (node (ref "C64") (pin "2") (pinfunction "2_2") (pintype "passive"))
      (node (ref "R93") (pin "1") (pinfunction "1_1") (pintype "passive"))
      (node (ref "R94") (pin "2") (pinfunction "2_2") (pintype "passive"))
      (node (ref "T12") (pin "1") (pinfunction "B_1") (pintype "passive"))
    )
    (net (code "125") (name "Net-(T14-D)") (class "Default")
      (node (ref "C51") (pin "2") (pinfunction "2_2") (pintype "passive"))
      (node (ref "L15") (pin "1") (pinfunction "1_1") (pintype "passive"))
      (node (ref "L16") (pin "1") (pinfunction "1_1") (pintype "passive"))
      (node (ref "T14") (pin "3") (pinfunction "D_3") (pintype "passive"))
    )
    (net (code "126") (name "Net-(T14-G)") (class "Default")
      (node (ref "L14") (pin "1") (pinfunction "1_1") (pintype "passive"))
      (node (ref "R97") (pin "2") (pinfunction "2_2") (pintype "passive"))
      (node (ref "T14") (pin "1") (pinfunction "G_1") (pintype "passive"))
    )
    (net (code "127") (name "Net-(T15-D)") (class "Default")
      (node (ref "C72") (pin "2") (pinfunction "2_2") (pintype "passive"))
      (node (ref "L19") (pin "1") (pinfunction "1_1") (pintype "passive"))
      (node (ref "L20") (pin "1") (pinfunction "1_1") (pintype "passive"))
      (node (ref "T15") (pin "3") (pinfunction "D_3") (pintype "passive"))
    )
    (net (code "128") (name "Net-(T15-G)") (class "Default")
      (node (ref "L18") (pin "1") (pinfunction "1_1") (pintype "passive"))
      (node (ref "R105") (pin "2") (pinfunction "2_2") (pintype "passive"))
      (node (ref "T15") (pin "1") (pinfunction "G_1") (pintype "passive"))
    )
    (net (code "129") (name "Net-(U1-PB6)") (class "Default")
      (node (ref "C66") (pin "2") (pinfunction "2_2") (pintype "passive"))
      (node (ref "Q11") (pin "1") (pinfunction "1_1") (pintype "passive"))
      (node (ref "U1") (pin "7") (pinfunction "PB6_7") (pintype "bidirectional"))
    )
    (net (code "130") (name "Net-(U1-PB7)") (class "Default")
      (node (ref "C65") (pin "2") (pinfunction "2_2") (pintype "passive"))
      (node (ref "Q11") (pin "2") (pinfunction "2_2") (pintype "passive"))
      (node (ref "U1") (pin "8") (pinfunction "PB7_8") (pintype "bidirectional"))
    )
    (net (code "131") (name "OUT") (class "Default")
      (node (ref "C35") (pin "2") (pinfunction "2_2") (pintype "passive"))
      (node (ref "C37") (pin "2") (pinfunction "2_2") (pintype "passive"))
      (node (ref "L8") (pin "1") (pinfunction "1_1") (pintype "passive"))
      (node (ref "R18") (pin "1") (pinfunction "1_1") (pintype "passive"))
    )
    (net (code "132") (name "OVR") (class "Default")
      (node (ref "R65") (pin "2") (pinfunction "2_2") (pintype "passive"))
      (node (ref "T11") (pin "2") (pinfunction "S_2") (pintype "passive"))
      (node (ref "T9") (pin "1") (pinfunction "G_1") (pintype "passive"))
      (node (ref "X2") (pin "RC") (pinfunction "RC_RC") (pintype "passive"))
    )
    (net (code "133") (name "OVR_INT") (class "Default")
      (node (ref "IC17") (pin "6") (pinfunction "S_6") (pintype "power_in"))
      (node (ref "IC6") (pin "6") (pinfunction "S_6") (pintype "power_in"))
      (node (ref "J106") (pin "1") (pinfunction "1_1") (pintype "passive"))
      (node (ref "J106") (pin "2") (pinfunction "2_2") (pintype "passive"))
      (node (ref "R12") (pin "1") (pinfunction "1_1") (pintype "passive"))
      (node (ref "R64") (pin "1") (pinfunction "1_1") (pintype "passive"))
      (node (ref "T8") (pin "3") (pinfunction "D_3") (pintype "passive"))
    )
    (net (code "134") (name "PA") (class "Default")
      (node (ref "C26") (pin "2") (pinfunction "2_2") (pintype "passive"))
      (node (ref "C36") (pin "2") (pinfunction "2_2") (pintype "passive"))
      (node (ref "C38") (pin "2") (pinfunction "2_2") (pintype "passive"))
      (node (ref "C68") (pin "2") (pinfunction "2_2") (pintype "passive"))
      (node (ref "IC3") (pin "1") (pinfunction "B2_1") (pintype "power_in"))
      (node (ref "L11") (pin "2") (pinfunction "2_2") (pintype "passive"))
    )
    (net (code "136") (name "PWR_SAVE") (class "Default")
      (node (ref "R119") (pin "1") (pinfunction "1_1") (pintype "passive"))
      (node (ref "R120") (pin "2") (pinfunction "2_2") (pintype "passive"))
      (node (ref "R121") (pin "1") (pinfunction "1_1") (pintype "passive"))
      (node (ref "T10") (pin "1") (pinfunction "G_1") (pintype "passive"))
      (node (ref "T13") (pin "1") (pinfunction "G_1") (pintype "passive"))
      (node (ref "T7") (pin "1") (pinfunction "G_1") (pintype "passive"))
    )
    (net (code "137") (name "PWR_SAVE_PROC") (class "Default")
      (node (ref "D6") (pin "C") (pinfunction "K_C") (pintype "passive"))
      (node (ref "R121") (pin "2") (pinfunction "2_2") (pintype "passive"))
      (node (ref "U1") (pin "10") (pinfunction "PD6_10") (pintype "bidirectional"))
    )
    (net (code "138") (name "RST") (class "Default")
      (node (ref "JP4") (pin "6") (pinfunction "6_6") (pintype "passive"))
      (node (ref "R72") (pin "1") (pinfunction "1_1") (pintype "passive"))
      (node (ref "U1") (pin "29") (pinfunction "PC6_29") (pintype "bidirectional"))
    )
    (net (code "139") (name "S0") (class "Default")
      (node (ref "IC1") (pin "6") (pinfunction "S0_6") (pintype "passive"))
      (node (ref "JP2") (pin "2") (pinfunction "2_2") (pintype "passive"))
    )
    (net (code "140") (name "S1") (class "Default")
      (node (ref "IC1") (pin "4") (pinfunction "S1_4") (pintype "power_in"))
      (node (ref "JP1") (pin "2") (pinfunction "2_2") (pintype "passive"))
    )
    (net (code "141") (name "SCK") (class "Default")
      (node (ref "IC10") (pin "2") (pinfunction "A_2") (pintype "bidirectional"))
      (node (ref "IC5") (pin "3") (pinfunction "SCK_3") (pintype "input"))
      (node (ref "J103") (pin "1") (pinfunction "1_1") (pintype "passive"))
      (node (ref "J103") (pin "2") (pinfunction "2_2") (pintype "passive"))
      (node (ref "JP4") (pin "4") (pinfunction "4_4") (pintype "passive"))
      (node (ref "U1") (pin "17") (pinfunction "PB5_17") (pintype "bidirectional"))
    )
    (net (code "142") (name "SCL") (class "Default")
      (node (ref "IC2") (pin "2") (pinfunction "SCL_2") (pintype "bidirectional"))
      (node (ref "R57") (pin "1") (pinfunction "1_1") (pintype "passive"))
      (node (ref "U1") (pin "28") (pinfunction "PC5_28") (pintype "bidirectional"))
    )
    (net (code "143") (name "SDA") (class "Default")
      (node (ref "IC2") (pin "1") (pinfunction "SDA_1") (pintype "bidirectional"))
      (node (ref "R56") (pin "1") (pinfunction "1_1") (pintype "passive"))
      (node (ref "U1") (pin "27") (pinfunction "PC4_27") (pintype "bidirectional"))
    )
    (net (code "144") (name "SIN_PWM") (class "Default")
      (node (ref "R50") (pin "2") (pinfunction "2_2") (pintype "passive"))
      (node (ref "R52") (pin "2") (pinfunction "2_2") (pintype "passive"))
      (node (ref "U1") (pin "1") (pinfunction "PD3_1") (pintype "bidirectional"))
    )
    (net (code "145") (name "VCAP") (class "Default")
      (node (ref "C3") (pin "2") (pinfunction "2_2") (pintype "passive"))
      (node (ref "IC15") (pin "7") (pinfunction "OUT_7") (pintype "output"))
      (node (ref "L4") (pin "1") (pinfunction "1_1") (pintype "passive"))
      (node (ref "R69") (pin "2") (pinfunction "2_2") (pintype "passive"))
      (node (ref "R81") (pin "2") (pinfunction "2_2") (pintype "passive"))
    )
    (net (code "146") (name "VCC") (class "Default")
      (node (ref "C10") (pin "2") (pinfunction "2_2") (pintype "passive"))
      (node (ref "C2") (pin "2") (pinfunction "2_2") (pintype "passive"))
      (node (ref "C24") (pin "+") (pinfunction "+_+") (pintype "passive"))
      (node (ref "C34") (pin "2") (pinfunction "2_2") (pintype "passive"))
      (node (ref "C47") (pin "+") (pinfunction "+_+") (pintype "passive"))
      (node (ref "C49") (pin "1") (pinfunction "1_1") (pintype "passive"))
      (node (ref "C5") (pin "2") (pinfunction "2_2") (pintype "passive"))
      (node (ref "D4") (pin "A") (pinfunction "A_A") (pintype "passive"))
      (node (ref "IC12") (pin "3") (pinfunction "VO_3") (pintype "output"))
      (node (ref "IC13") (pin "1") (pinfunction "VIN_1") (pintype "input"))
      (node (ref "IC18") (pin "8") (pinfunction "VIN_8") (pintype "input"))
      (node (ref "IC2") (pin "8") (pinfunction "VDD_8") (pintype "power_in"))
      (node (ref "IC3") (pin "5") (pinfunction "VCC_5") (pintype "input"))
      (node (ref "IC5") (pin "1") (pinfunction "VDD_1") (pintype "power_in"))
      (node (ref "JP4") (pin "9") (pinfunction "9_9") (pintype "passive"))
      (node (ref "L13") (pin "2") (pinfunction "2_2") (pintype "passive"))
      (node (ref "L5") (pin "2") (pinfunction "2_2") (pintype "passive"))
      (node (ref "R1") (pin "1") (pinfunction "1_1") (pintype "passive"))
      (node (ref "R119") (pin "2") (pinfunction "2_2") (pintype "passive"))
      (node (ref "R48") (pin "2") (pinfunction "2_2") (pintype "passive"))
      (node (ref "R56") (pin "2") (pinfunction "2_2") (pintype "passive"))
      (node (ref "R57") (pin "2") (pinfunction "2_2") (pintype "passive"))
      (node (ref "R63") (pin "2") (pinfunction "2_2") (pintype "passive"))
      (node (ref "R67") (pin "1") (pinfunction "1_1") (pintype "passive"))
      (node (ref "R72") (pin "2") (pinfunction "2_2") (pintype "passive"))
      (node (ref "R79") (pin "1") (pinfunction "1_1") (pintype "passive"))
      (node (ref "R95") (pin "1") (pinfunction "1_1") (pintype "passive"))
      (node (ref "T13") (pin "2") (pinfunction "S_2") (pintype "passive"))
      (node (ref "T8") (pin "2") (pinfunction "S_2") (pintype "passive"))
      (node (ref "U1") (pin "18") (pinfunction "AVCC_18") (pintype "power_in"))
      (node (ref "U1") (pin "20") (pinfunction "AREF_20") (pintype "input"))
      (node (ref "U1") (pin "4") (pinfunction "VCC_2_4") (pintype "power_in"))
      (node (ref "U1") (pin "6") (pinfunction "VCC_6") (pintype "power_in"))
    )
    (net (code "147") (name "VSS") (class "Default")
      (node (ref "C15") (pin "-") (pinfunction "-_-") (pintype "passive"))
      (node (ref "IC14") (pin "4") (pinfunction "-VO_4") (pintype "output"))
      (node (ref "IC15") (pin "4") (pinfunction "GND_4") (pintype "power_in"))
      (node (ref "IC8") (pin "4") (pinfunction "GND_4") (pintype "power_in"))
      (node (ref "IC9") (pin "4") (pinfunction "GND_4") (pintype "power_in"))
      (node (ref "R2") (pin "1") (pinfunction "1_1") (pintype "passive"))
    )
    (net (code "148") (name "unconnected-(IC2-NC-Pad3)") (class "Default")
      (node (ref "IC2") (pin "3") (pinfunction "NC_3") (pintype "no_connect"))
    )
    (net (code "149") (name "unconnected-(IC4-R-Pad1)") (class "Default")
      (node (ref "IC4") (pin "1") (pinfunction "R_1") (pintype "bidirectional"))
    )
    (net (code "150") (name "unconnected-(IC4-R2-Pad17)") (class "Default")
      (node (ref "IC4") (pin "17") (pinfunction "R2_17") (pintype "bidirectional"))
    )
    (net (code "151") (name "unconnected-(IC18-BOOST-Pad1)") (class "Default")
      (node (ref "IC18") (pin "1") (pinfunction "BOOST_1") (pintype "passive"))
    )
    (net (code "152") (name "unconnected-(IC18-LV-Pad6)") (class "Default")
      (node (ref "IC18") (pin "6") (pinfunction "LV_6") (pintype "passive"))
    )
    (net (code "153") (name "unconnected-(IC18-OSC-Pad7)") (class "Default")
      (node (ref "IC18") (pin "7") (pinfunction "OSC_7") (pintype "passive"))
    )
    (net (code "154") (name "unconnected-(J1-Pad2)") (class "Default")
      (node (ref "J1") (pin "2") (pinfunction "2_2") (pintype "passive"))
    )
    (net (code "155") (name "unconnected-(JP4-Pad8)") (class "Default")
      (node (ref "JP4") (pin "8") (pinfunction "8_8") (pintype "passive"))
    )
    (net (code "156") (name "unconnected-(R73-Pad1)") (class "Default")
      (node (ref "R73") (pin "1") (pinfunction "1_1") (pintype "passive"))
    )
    (net (code "157") (name "unconnected-(R77-Pad1)") (class "Default")
      (node (ref "R77") (pin "1") (pinfunction "1_1") (pintype "passive"))
    )
    (net (code "158") (name "unconnected-(R86-Pad1)") (class "Default")
      (node (ref "R86") (pin "1") (pinfunction "1_1") (pintype "passive"))
    )
    (net (code "159") (name "unconnected-(R87-Pad1)") (class "Default")
      (node (ref "R87") (pin "1") (pinfunction "1_1") (pintype "passive"))
    )
    (net (code "160") (name "unconnected-(R89-Pad1)") (class "Default")
      (node (ref "R89") (pin "1") (pinfunction "1_1") (pintype "passive"))
    )
    (net (code "161") (name "unconnected-(R90-Pad1)") (class "Default")
      (node (ref "R90") (pin "1") (pinfunction "1_1") (pintype "passive"))
    )
    (net (code "162") (name "unconnected-(R91-Pad1)") (class "Default")
      (node (ref "R91") (pin "1") (pinfunction "1_1") (pintype "passive"))
    )
    (net (code "163") (name "unconnected-(R92-Pad1)") (class "Default")
      (node (ref "R92") (pin "1") (pinfunction "1_1") (pintype "passive"))
    )
    (net (code "164") (name "unconnected-(R111-Pad1)") (class "Default")
      (node (ref "R111") (pin "1") (pinfunction "1_1") (pintype "passive"))
    )
    (net (code "165") (name "unconnected-(R111-Pad2)") (class "Default")
      (node (ref "R111") (pin "2") (pinfunction "2_2") (pintype "passive"))
    )
    (net (code "166") (name "unconnected-(R112-Pad1)") (class "Default")
      (node (ref "R112") (pin "1") (pinfunction "1_1") (pintype "passive"))
    )
    (net (code "167") (name "unconnected-(R112-Pad2)") (class "Default")
      (node (ref "R112") (pin "2") (pinfunction "2_2") (pintype "passive"))
    )
    (net (code "168") (name "unconnected-(R113-Pad1)") (class "Default")
      (node (ref "R113") (pin "1") (pinfunction "1_1") (pintype "passive"))
    )
    (net (code "169") (name "unconnected-(R113-Pad2)") (class "Default")
      (node (ref "R113") (pin "2") (pinfunction "2_2") (pintype "passive"))
    )
    (net (code "170") (name "unconnected-(R114-Pad1)") (class "Default")
      (node (ref "R114") (pin "1") (pinfunction "1_1") (pintype "passive"))
    )
    (net (code "171") (name "unconnected-(R114-Pad2)") (class "Default")
      (node (ref "R114") (pin "2") (pinfunction "2_2") (pintype "passive"))
    )
    (net (code "172") (name "unconnected-(R115-Pad1)") (class "Default")
      (node (ref "R115") (pin "1") (pinfunction "1_1") (pintype "passive"))
    )
    (net (code "173") (name "unconnected-(R115-Pad2)") (class "Default")
      (node (ref "R115") (pin "2") (pinfunction "2_2") (pintype "passive"))
    )
    (net (code "174") (name "unconnected-(R116-Pad1)") (class "Default")
      (node (ref "R116") (pin "1") (pinfunction "1_1") (pintype "passive"))
    )
    (net (code "175") (name "unconnected-(R116-Pad2)") (class "Default")
      (node (ref "R116") (pin "2") (pinfunction "2_2") (pintype "passive"))
    )
    (net (code "176") (name "unconnected-(R117-Pad1)") (class "Default")
      (node (ref "R117") (pin "1") (pinfunction "1_1") (pintype "passive"))
    )
    (net (code "177") (name "unconnected-(R117-Pad2)") (class "Default")
      (node (ref "R117") (pin "2") (pinfunction "2_2") (pintype "passive"))
    )
    (net (code "178") (name "unconnected-(R118-Pad1)") (class "Default")
      (node (ref "R118") (pin "1") (pinfunction "1_1") (pintype "passive"))
    )
    (net (code "179") (name "unconnected-(R118-Pad2)") (class "Default")
      (node (ref "R118") (pin "2") (pinfunction "2_2") (pintype "passive"))
    )
    (net (code "180") (name "unconnected-(SW1-Pad4)") (class "Default")
      (node (ref "SW1") (pin "4") (pinfunction "4_4") (pintype "passive"))
    )
    (net (code "181") (name "unconnected-(SW2-Pad4)") (class "Default")
      (node (ref "SW2") (pin "4") (pinfunction "4_4") (pintype "passive"))
    )
    (net (code "182") (name "unconnected-(T16-D-Pad3)") (class "Default")
      (node (ref "T16") (pin "3") (pinfunction "D_3") (pintype "passive"))
    )
    (net (code "183") (name "unconnected-(T16-G-Pad1)") (class "Default")
      (node (ref "T16") (pin "1") (pinfunction "G_1") (pintype "passive"))
    )
    (net (code "184") (name "unconnected-(T16-S-Pad2)") (class "Default")
      (node (ref "T16") (pin "2") (pinfunction "S_2") (pintype "passive"))
    )
    (net (code "185") (name "unconnected-(T17-D-Pad3)") (class "Default")
      (node (ref "T17") (pin "3") (pinfunction "D_3") (pintype "passive"))
    )
    (net (code "186") (name "unconnected-(T17-G-Pad1)") (class "Default")
      (node (ref "T17") (pin "1") (pinfunction "G_1") (pintype "passive"))
    )
    (net (code "187") (name "unconnected-(T17-S-Pad2)") (class "Default")
      (node (ref "T17") (pin "2") (pinfunction "S_2") (pintype "passive"))
    )
    (net (code "188") (name "unconnected-(T18-D-Pad3)") (class "Default")
      (node (ref "T18") (pin "3") (pinfunction "D_3") (pintype "passive"))
    )
    (net (code "189") (name "unconnected-(T18-G-Pad1)") (class "Default")
      (node (ref "T18") (pin "1") (pinfunction "G_1") (pintype "passive"))
    )
    (net (code "190") (name "unconnected-(T18-S-Pad2)") (class "Default")
      (node (ref "T18") (pin "2") (pinfunction "S_2") (pintype "passive"))
    )
    (net (code "191") (name "unconnected-(T19-D-Pad3)") (class "Default")
      (node (ref "T19") (pin "3") (pinfunction "D_3") (pintype "passive"))
    )
    (net (code "192") (name "unconnected-(T19-G-Pad1)") (class "Default")
      (node (ref "T19") (pin "1") (pinfunction "G_1") (pintype "passive"))
    )
    (net (code "193") (name "unconnected-(T19-S-Pad2)") (class "Default")
      (node (ref "T19") (pin "2") (pinfunction "S_2") (pintype "passive"))
    )
    (net (code "194") (name "unconnected-(U1-ADC6-Pad19)") (class "Default")
      (node (ref "U1") (pin "19") (pinfunction "ADC6_19") (pintype "input"))
    )
    (net (code "195") (name "unconnected-(U1-PB0-Pad12)") (class "Default")
      (node (ref "U1") (pin "12") (pinfunction "PB0_12") (pintype "bidirectional"))
    )
    (net (code "196") (name "unconnected-(U1-PB1-Pad13)") (class "Default")
      (node (ref "U1") (pin "13") (pinfunction "PB1_13") (pintype "bidirectional"))
    )
    (net (code "197") (name "unconnected-(U1-PD0-Pad30)") (class "Default")
      (node (ref "U1") (pin "30") (pinfunction "PD0_30") (pintype "bidirectional"))
    )
    (net (code "198") (name "unconnected-(U1-PD7-Pad11)") (class "Default")
      (node (ref "U1") (pin "11") (pinfunction "PD7_11") (pintype "bidirectional"))
    )
    (net (code "199") (name "unconnected-(X2-PadLC)") (class "Default")
      (node (ref "X2") (pin "LC") (pinfunction "LC_LC") (pintype "passive"))
    )
  )
)
